# TR4.net
KiCad netlist of a schematic drawn in EAGLE
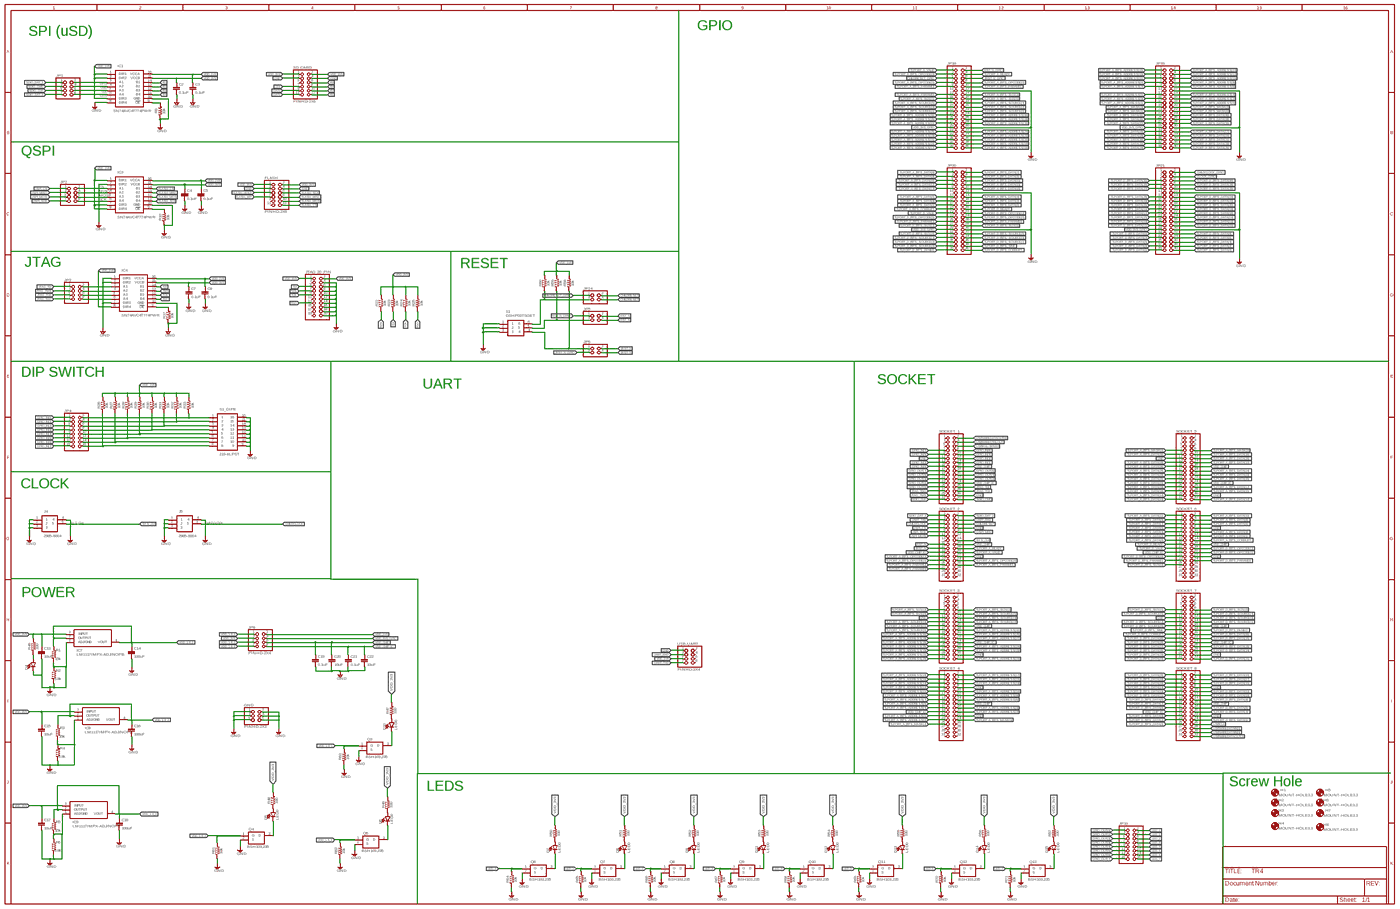
[diagram p0: schematic, sheet 1, overview]
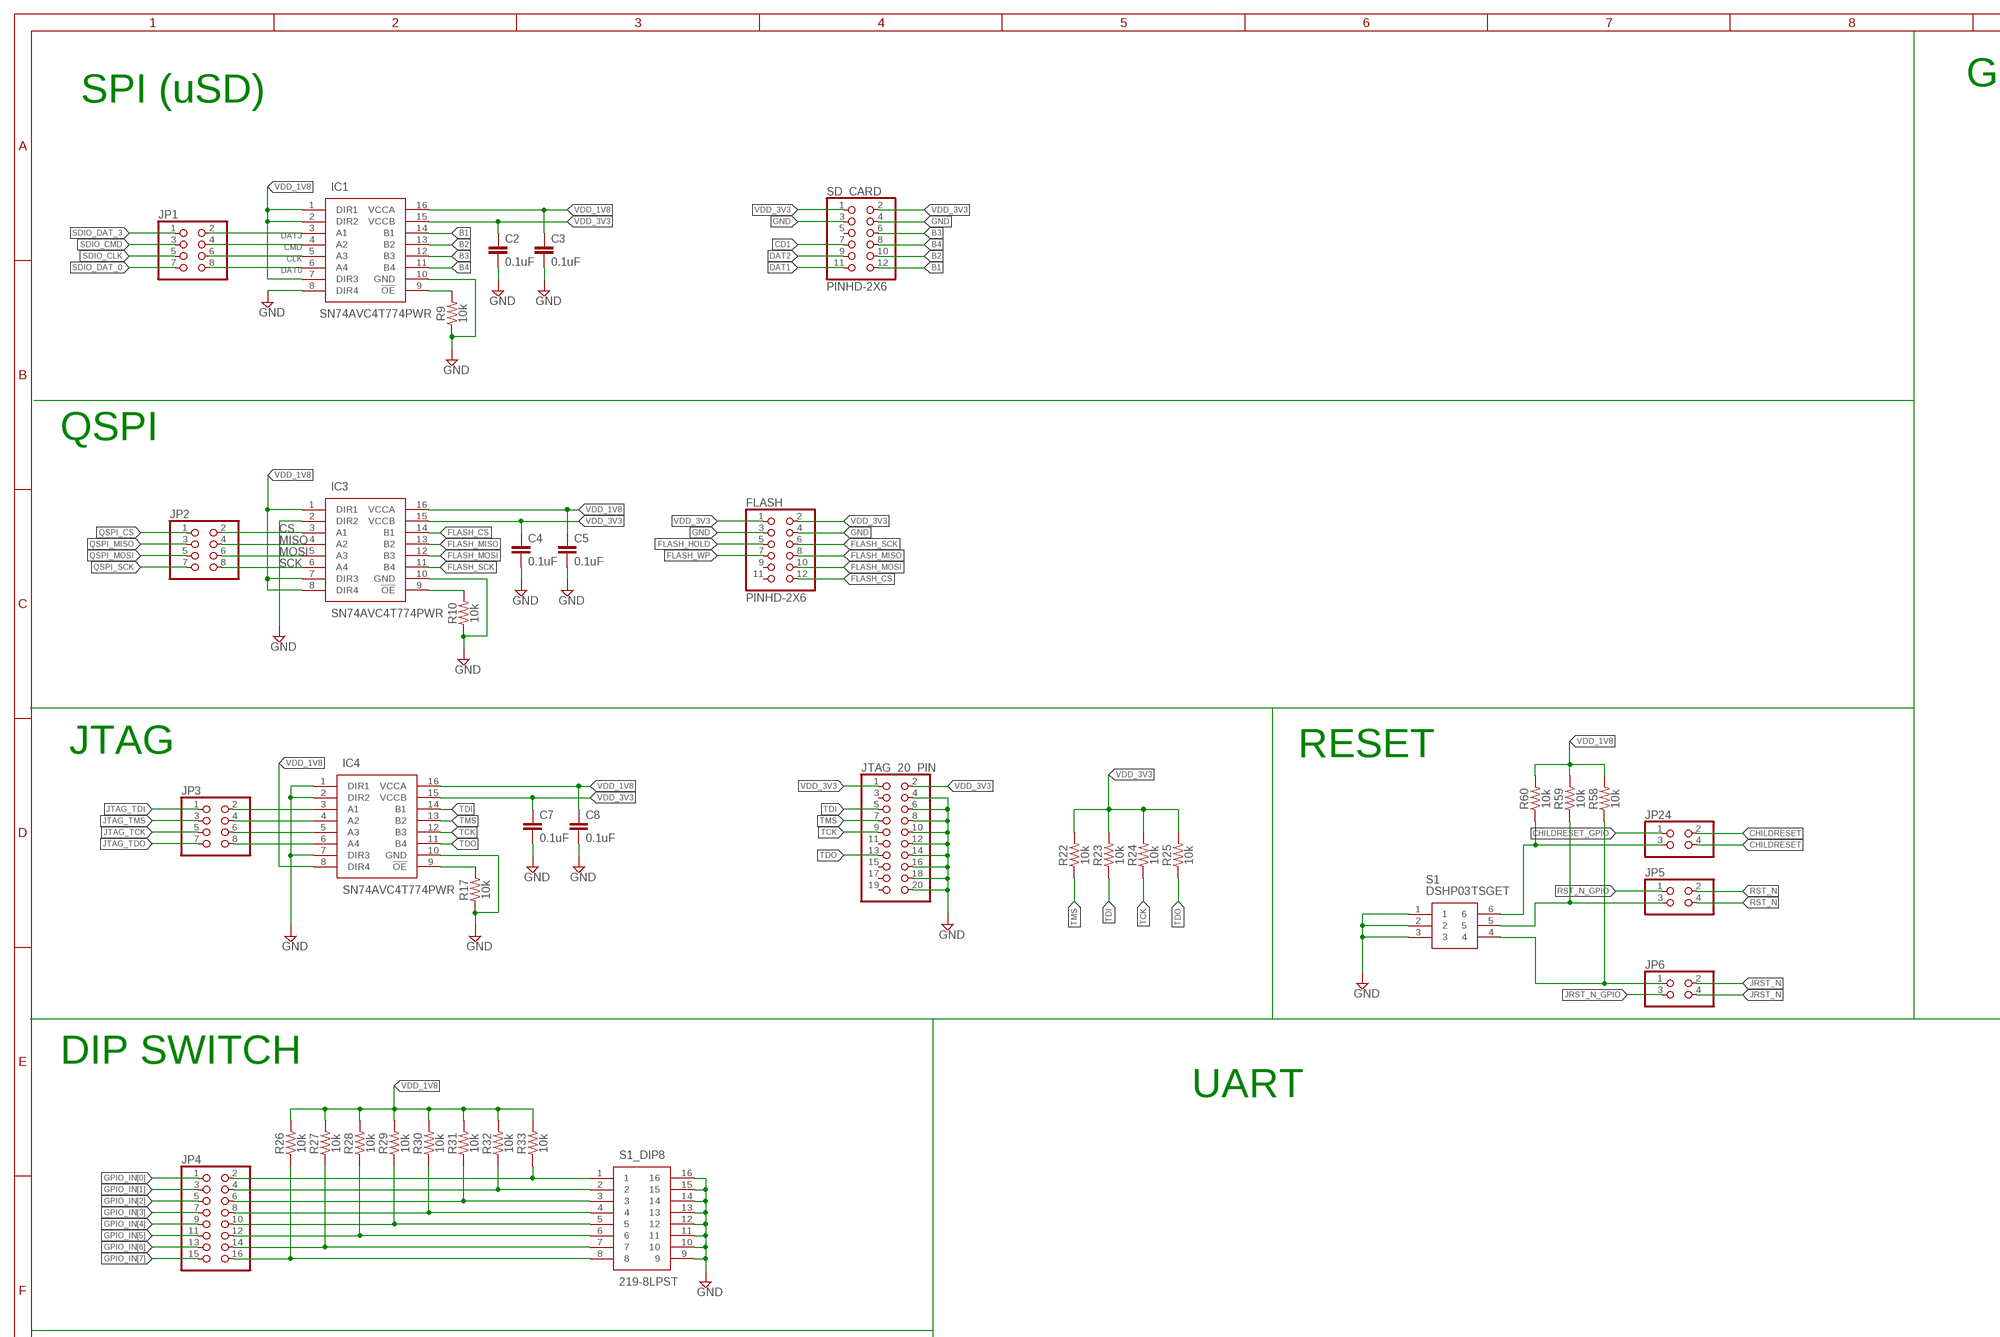
[diagram p1: schematic, sheet 1, part 1 of 4]
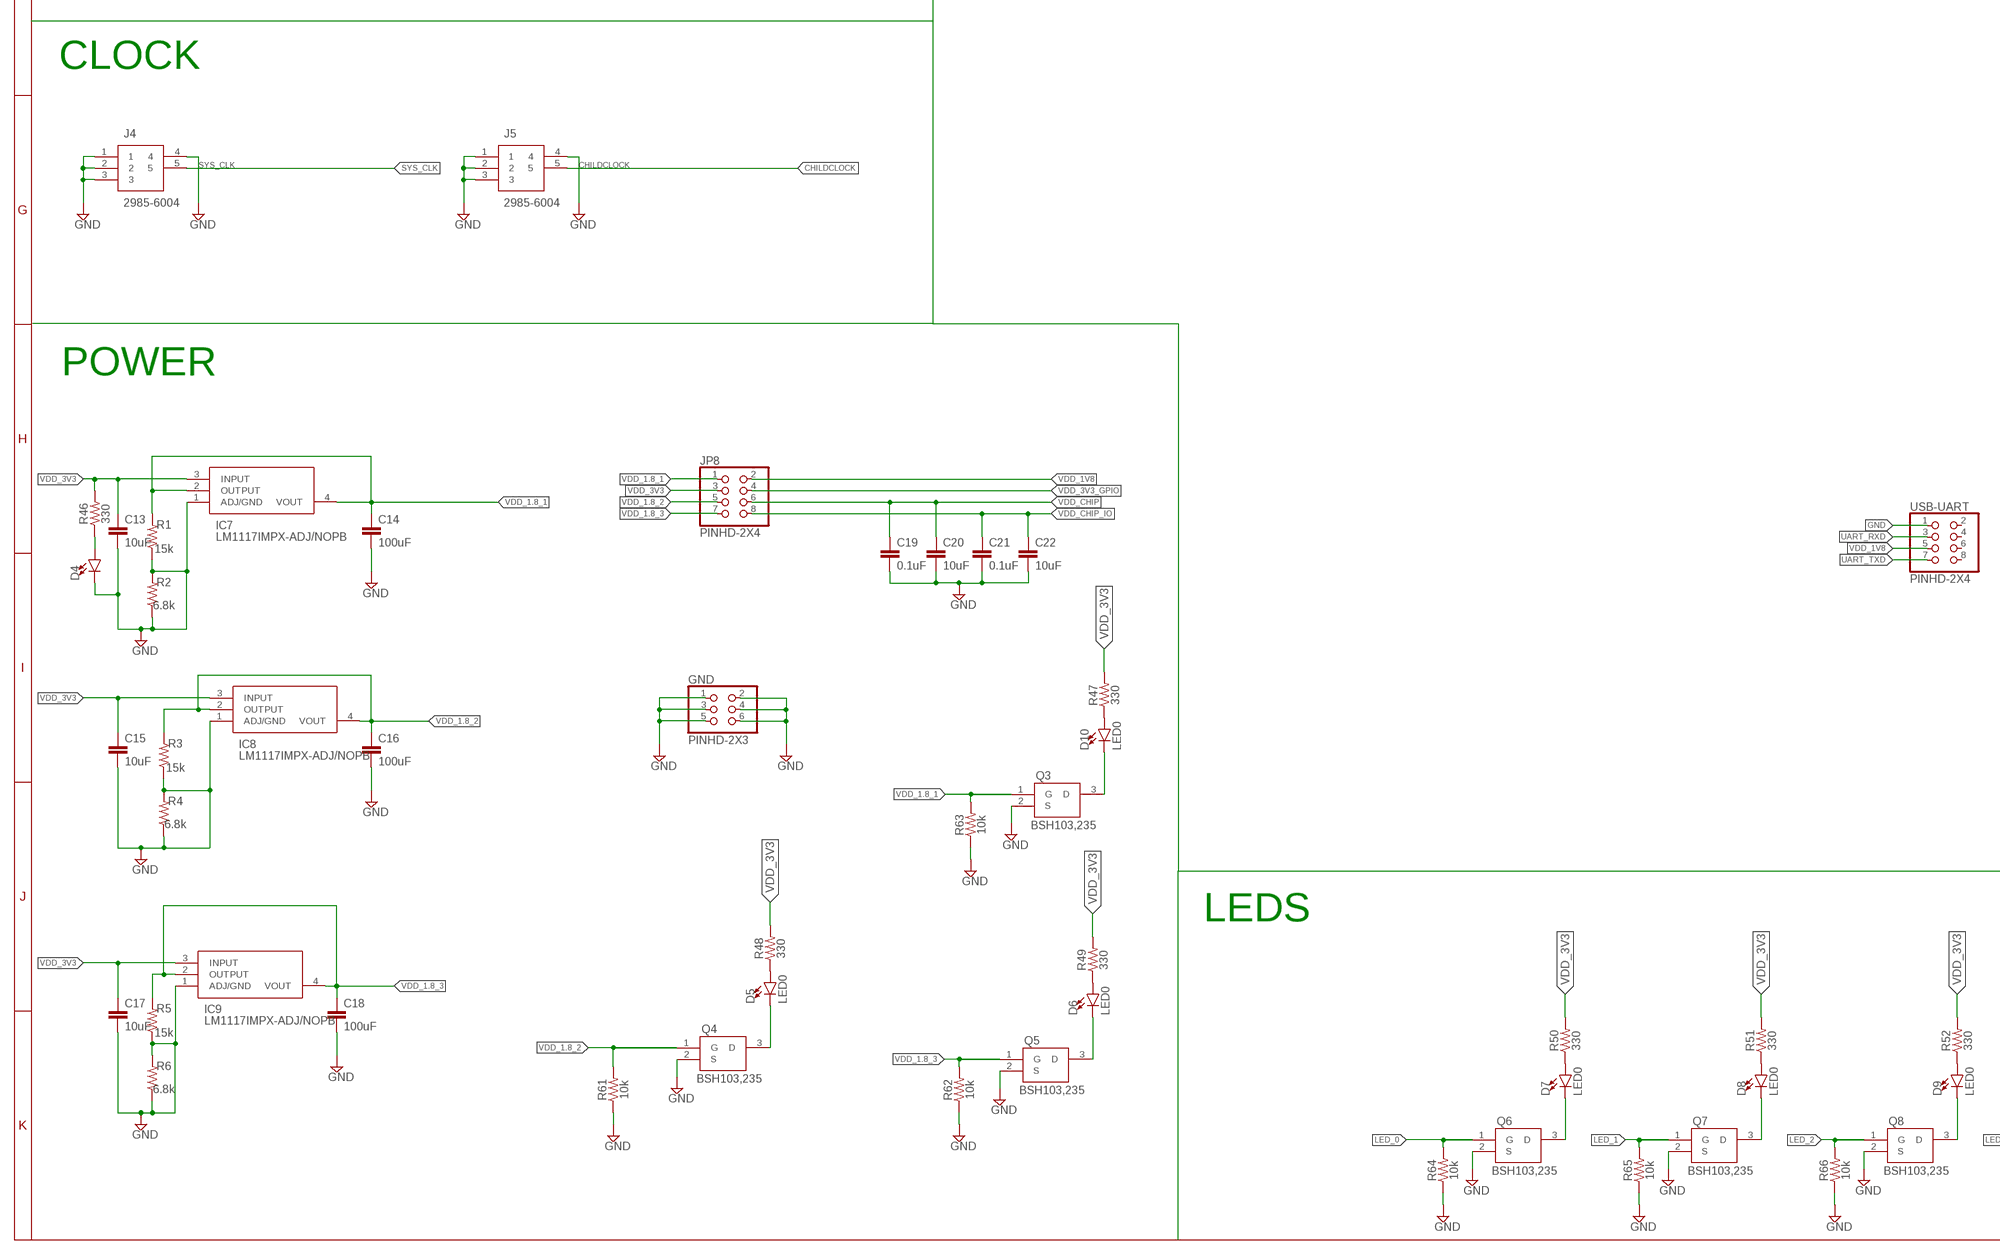
[diagram p2: schematic, sheet 1, part 2 of 4]
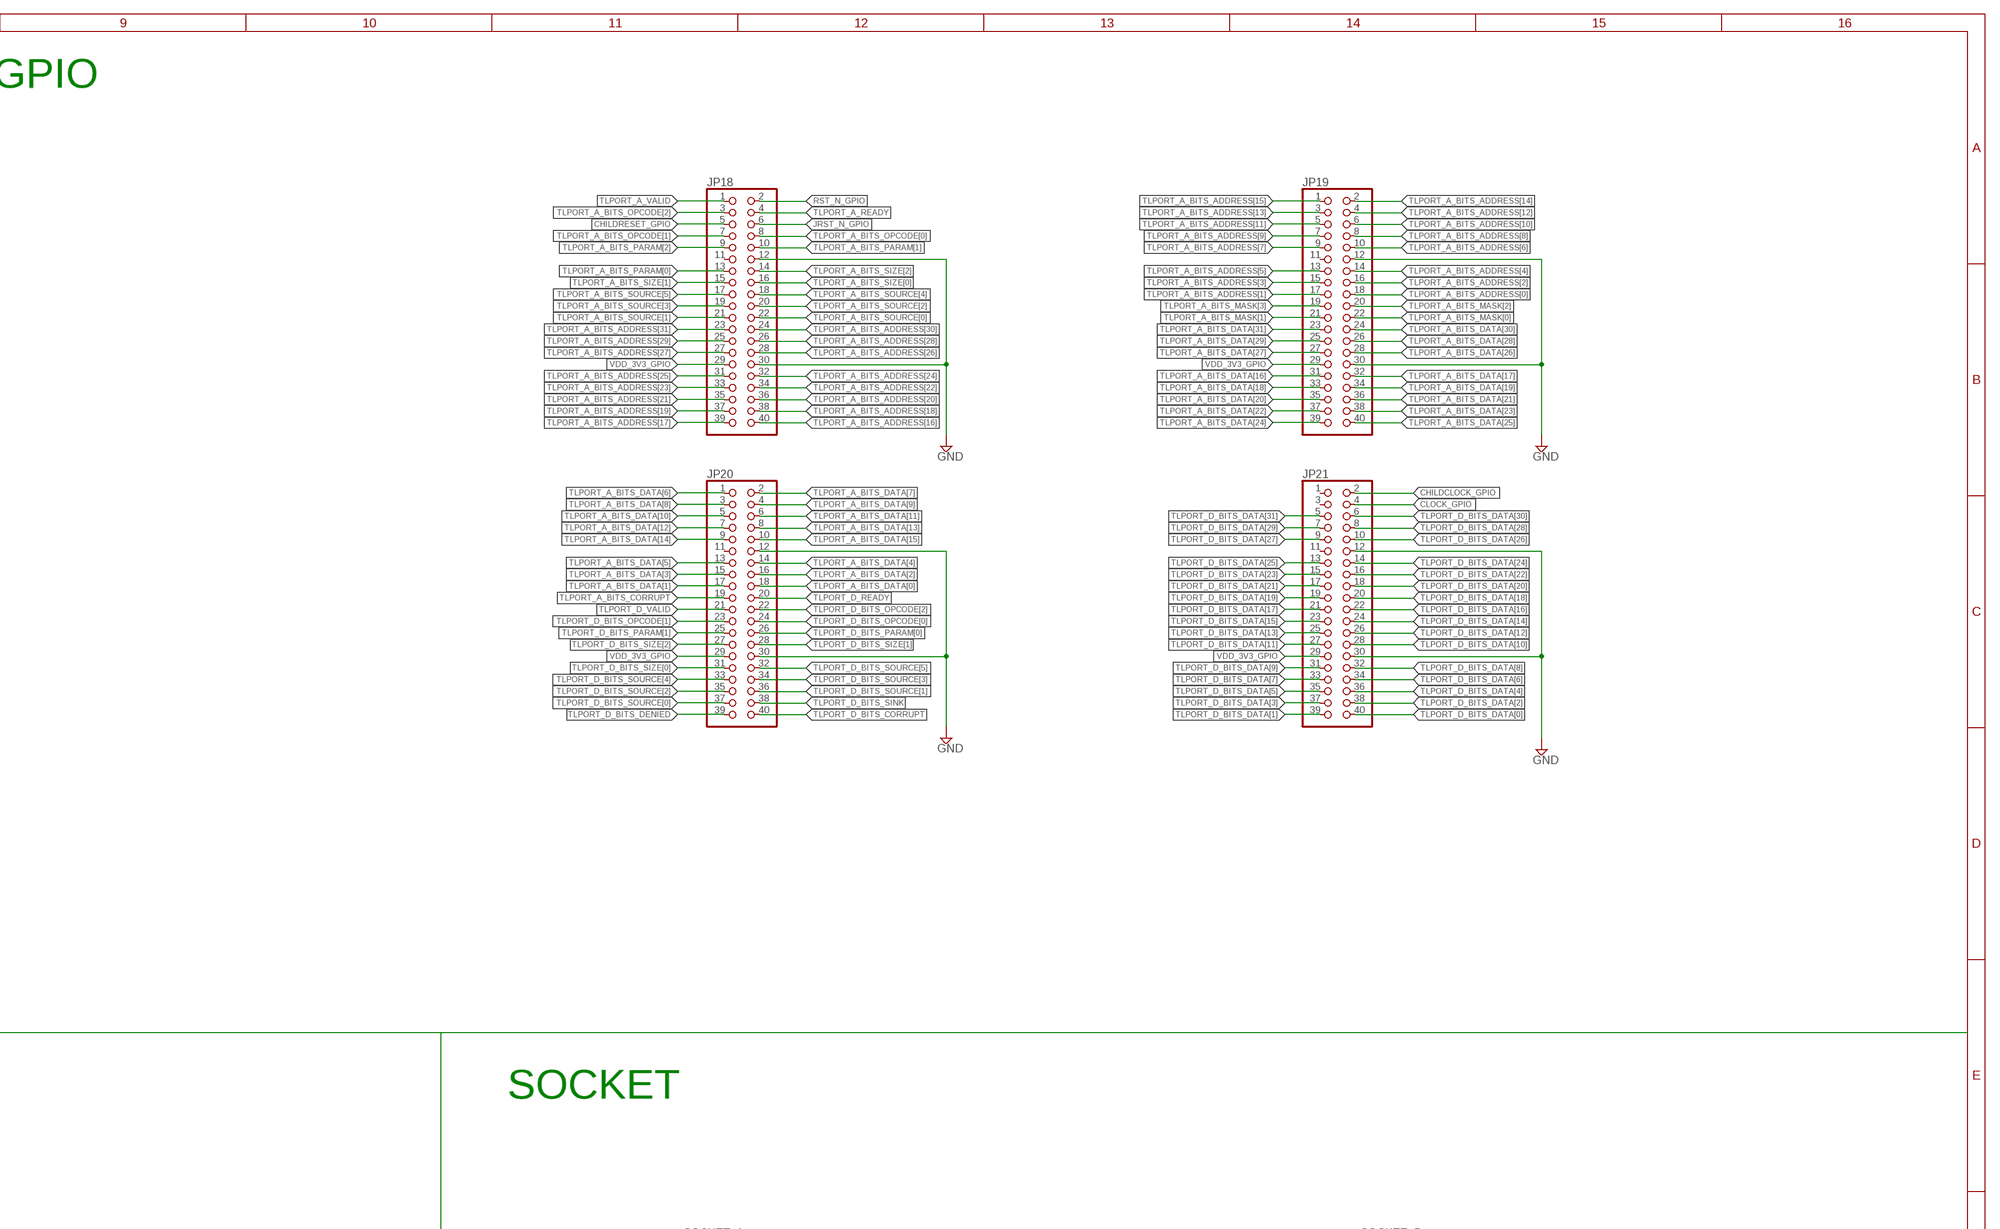
[diagram p3: schematic, sheet 1, part 3 of 4]
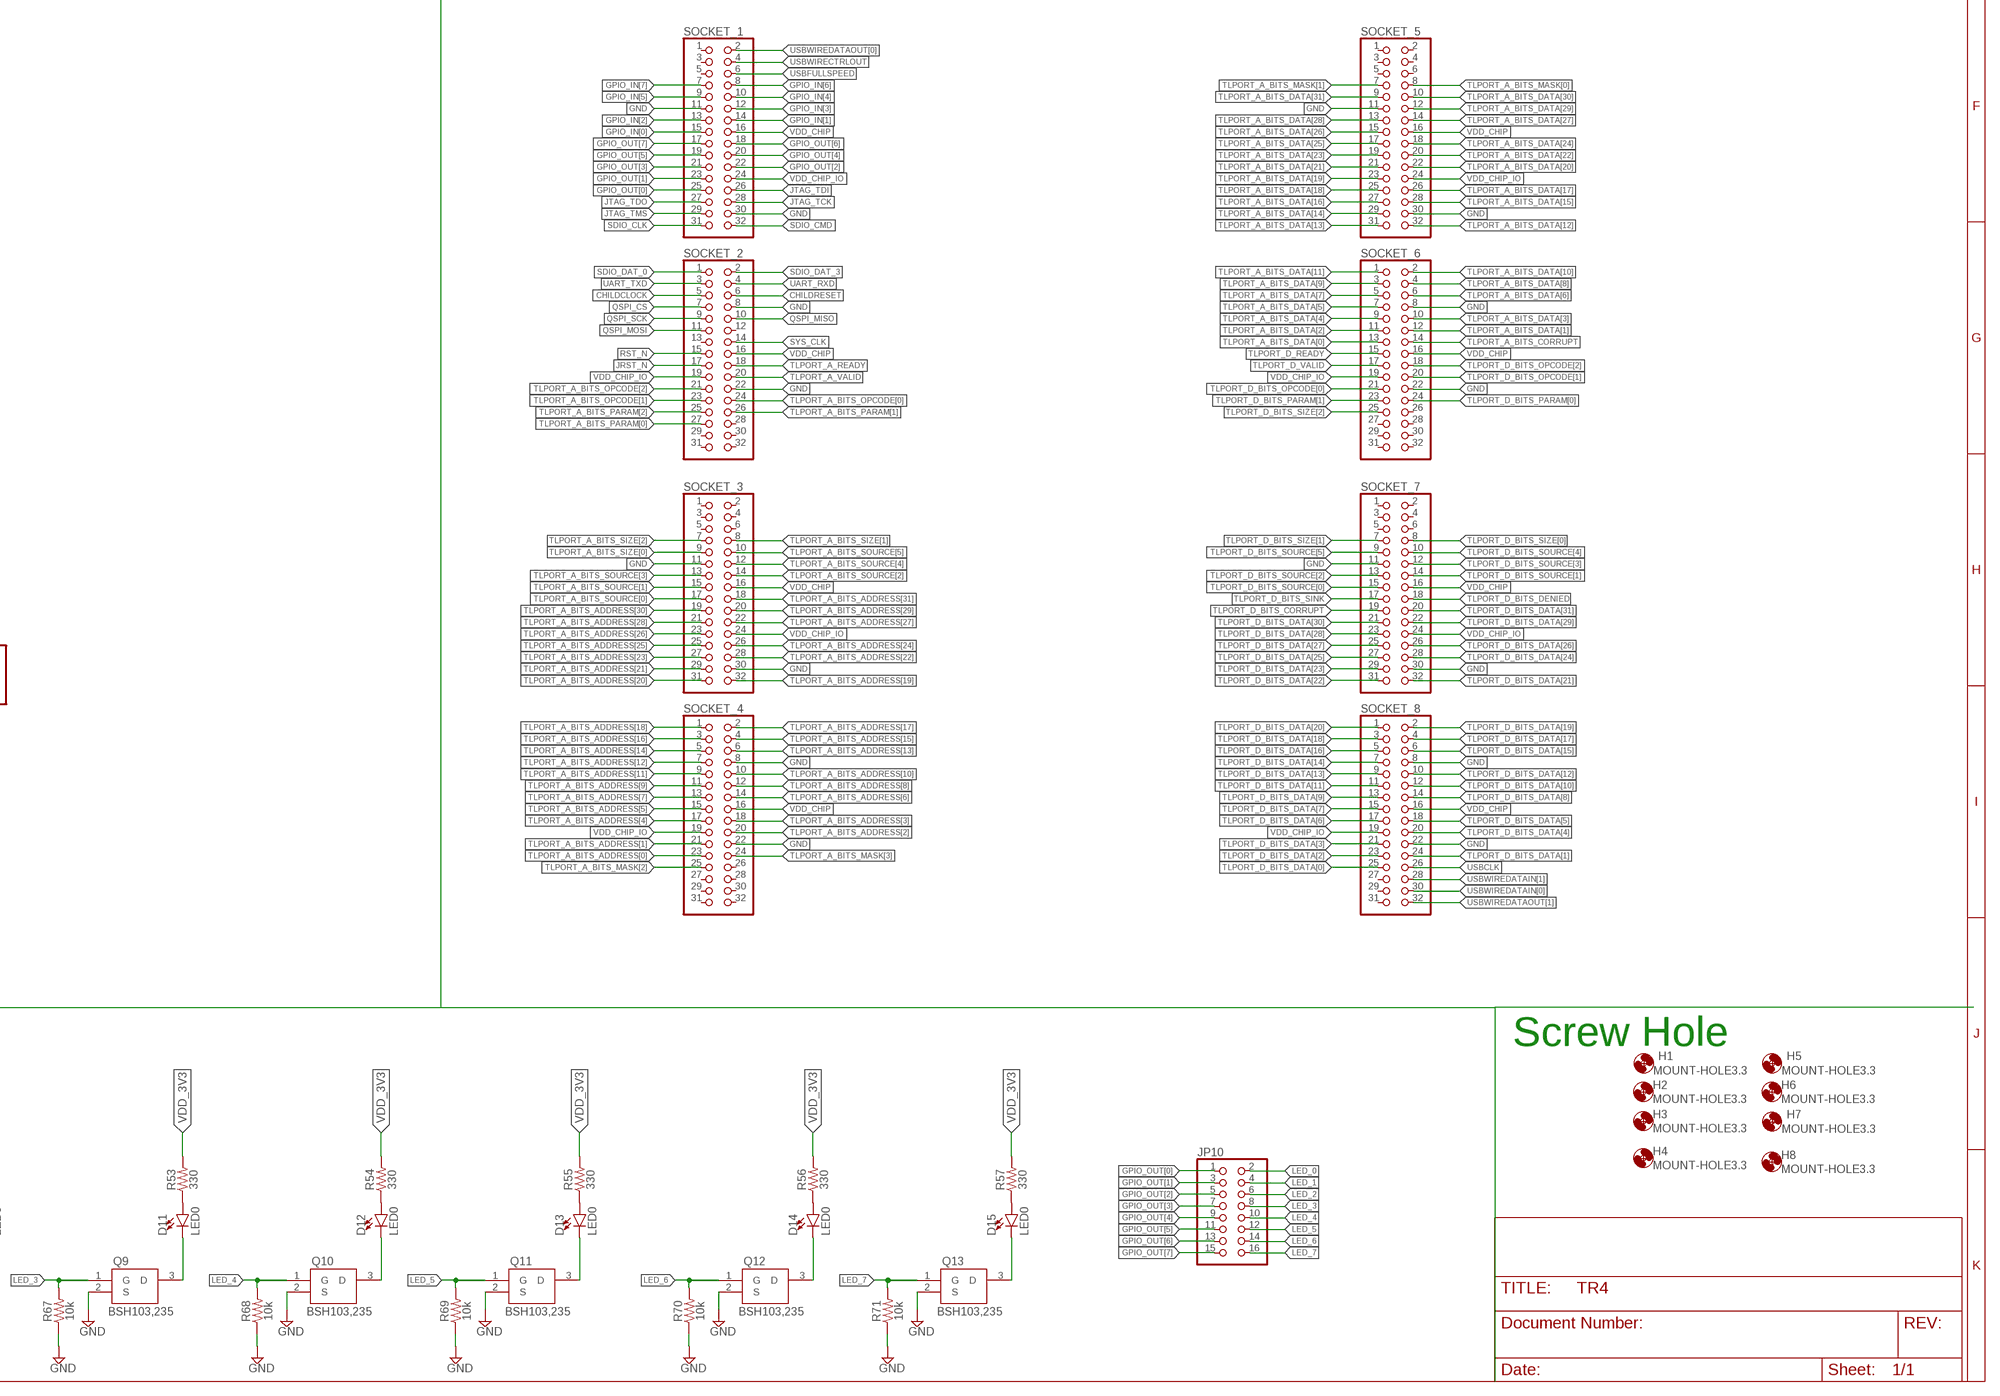
[diagram p4: schematic, sheet 1, part 4 of 4]

(export (version "E")
  (design (tool "Eeschema 10.0.6"))
  (components
    (comp (ref "C2")
      (value "0.1uF")
      (footprint "eagle-import:0603")
      (libsource (lib "eagle-import") (part "0.1UF-0603-25V-5%"))
    )
    (comp (ref "C3")
      (value "0.1uF")
      (footprint "eagle-import:0603")
      (libsource (lib "eagle-import") (part "0.1UF-0603-25V-5%"))
    )
    (comp (ref "C4")
      (value "0.1uF")
      (footprint "eagle-import:0603")
      (libsource (lib "eagle-import") (part "0.1UF-0603-25V-5%"))
    )
    (comp (ref "C5")
      (value "0.1uF")
      (footprint "eagle-import:0603")
      (libsource (lib "eagle-import") (part "0.1UF-0603-25V-5%"))
    )
    (comp (ref "C7")
      (value "0.1uF")
      (footprint "eagle-import:0603")
      (libsource (lib "eagle-import") (part "0.1UF-0603-25V-5%"))
    )
    (comp (ref "C8")
      (value "0.1uF")
      (footprint "eagle-import:0603")
      (libsource (lib "eagle-import") (part "0.1UF-0603-25V-5%"))
    )
    (comp (ref "C13")
      (value "10uF")
      (footprint "eagle-import:0603")
      (libsource (lib "eagle-import") (part "10UF-0603-6.3V-20%"))
    )
    (comp (ref "C14")
      (value "100uF")
      (footprint "eagle-import:0603")
      (libsource (lib "eagle-import") (part "10UF-0603-6.3V-20%"))
    )
    (comp (ref "C15")
      (value "10uF")
      (footprint "eagle-import:0603")
      (libsource (lib "eagle-import") (part "10UF-0603-6.3V-20%"))
    )
    (comp (ref "C16")
      (value "100uF")
      (footprint "eagle-import:0603")
      (libsource (lib "eagle-import") (part "10UF-0603-6.3V-20%"))
    )
    (comp (ref "C17")
      (value "10uF")
      (footprint "eagle-import:0603")
      (libsource (lib "eagle-import") (part "10UF-0603-6.3V-20%"))
    )
    (comp (ref "C18")
      (value "100uF")
      (footprint "eagle-import:0603")
      (libsource (lib "eagle-import") (part "10UF-0603-6.3V-20%"))
    )
    (comp (ref "C19")
      (value "0.1uF")
      (footprint "eagle-import:0603")
      (libsource (lib "eagle-import") (part "0.1UF-0603-25V-5%"))
    )
    (comp (ref "C20")
      (value "10uF")
      (footprint "eagle-import:0603")
      (libsource (lib "eagle-import") (part "10UF-0603-6.3V-20%"))
    )
    (comp (ref "C21")
      (value "0.1uF")
      (footprint "eagle-import:0603")
      (libsource (lib "eagle-import") (part "0.1UF-0603-25V-5%"))
    )
    (comp (ref "C22")
      (value "10uF")
      (footprint "eagle-import:0603")
      (libsource (lib "eagle-import") (part "10UF-0603-6.3V-20%"))
    )
    (comp (ref "D4")
      (value "LED0603")
      (footprint "eagle-import:LED-0603")
      (libsource (lib "eagle-import") (part "LED0603"))
    )
    (comp (ref "D5")
      (value "LED0")
      (footprint "eagle-import:LED-0603")
      (libsource (lib "eagle-import") (part "LED0603"))
    )
    (comp (ref "D6")
      (value "LED0")
      (footprint "eagle-import:LED-0603")
      (libsource (lib "eagle-import") (part "LED0603"))
    )
    (comp (ref "D7")
      (value "LED0")
      (footprint "eagle-import:LED-0603")
      (libsource (lib "eagle-import") (part "LED0603"))
    )
    (comp (ref "D8")
      (value "LED0")
      (footprint "eagle-import:LED-0603")
      (libsource (lib "eagle-import") (part "LED0603"))
    )
    (comp (ref "D9")
      (value "LED0")
      (footprint "eagle-import:LED-0603")
      (libsource (lib "eagle-import") (part "LED0603"))
    )
    (comp (ref "D10")
      (value "LED0")
      (footprint "eagle-import:LED-0603")
      (libsource (lib "eagle-import") (part "LED0603"))
    )
    (comp (ref "D11")
      (value "LED0")
      (footprint "eagle-import:LED-0603")
      (libsource (lib "eagle-import") (part "LED0603"))
    )
    (comp (ref "D12")
      (value "LED0")
      (footprint "eagle-import:LED-0603")
      (libsource (lib "eagle-import") (part "LED0603"))
    )
    (comp (ref "D13")
      (value "LED0")
      (footprint "eagle-import:LED-0603")
      (libsource (lib "eagle-import") (part "LED0603"))
    )
    (comp (ref "D14")
      (value "LED0")
      (footprint "eagle-import:LED-0603")
      (libsource (lib "eagle-import") (part "LED0603"))
    )
    (comp (ref "D15")
      (value "LED0")
      (footprint "eagle-import:LED-0603")
      (libsource (lib "eagle-import") (part "LED0603"))
    )
    (comp (ref "FLASH")
      (value "PINHD-2X6")
      (footprint "eagle-import:2X06")
      (libsource (lib "eagle-import") (part "PINHD-2X6"))
    )
    (comp (ref "GND")
      (value "PINHD-2X3")
      (footprint "eagle-import:2X03")
      (libsource (lib "eagle-import") (part "PINHD-2X3"))
    )
    (comp (ref "H1")
      (value "MOUNT-HOLE3.3")
      (footprint "eagle-import:3,3")
      (libsource (lib "eagle-import") (part "MOUNT-HOLE3.3"))
    )
    (comp (ref "H2")
      (value "MOUNT-HOLE3.3")
      (footprint "eagle-import:3,3")
      (libsource (lib "eagle-import") (part "MOUNT-HOLE3.3"))
    )
    (comp (ref "H3")
      (value "MOUNT-HOLE3.3")
      (footprint "eagle-import:3,3")
      (libsource (lib "eagle-import") (part "MOUNT-HOLE3.3"))
    )
    (comp (ref "H4")
      (value "MOUNT-HOLE3.3")
      (footprint "eagle-import:3,3")
      (libsource (lib "eagle-import") (part "MOUNT-HOLE3.3"))
    )
    (comp (ref "H5")
      (value "MOUNT-HOLE3.3")
      (footprint "eagle-import:3,3")
      (libsource (lib "eagle-import") (part "MOUNT-HOLE3.3"))
    )
    (comp (ref "H6")
      (value "MOUNT-HOLE3.3")
      (footprint "eagle-import:3,3")
      (libsource (lib "eagle-import") (part "MOUNT-HOLE3.3"))
    )
    (comp (ref "H7")
      (value "MOUNT-HOLE3.3")
      (footprint "eagle-import:3,3")
      (libsource (lib "eagle-import") (part "MOUNT-HOLE3.3"))
    )
    (comp (ref "H8")
      (value "MOUNT-HOLE3.3")
      (footprint "eagle-import:3,3")
      (libsource (lib "eagle-import") (part "MOUNT-HOLE3.3"))
    )
    (comp (ref "IC1")
      (value "SN74AVC4T774PWR")
      (footprint "eagle-import:SOP65P640X120-16N")
      (fields (field (name "MOUSER_PART_NUMBER") "595-SN74AVC4T774PWR"))
      (libsource (lib "eagle-import") (part "SN74AVC4T774PWR"))
    )
    (comp (ref "IC3")
      (value "SN74AVC4T774PWR")
      (footprint "eagle-import:SOP65P640X120-16N")
      (fields (field (name "MOUSER_PART_NUMBER") "595-SN74AVC4T774PWR"))
      (libsource (lib "eagle-import") (part "SN74AVC4T774PWR"))
    )
    (comp (ref "IC4")
      (value "SN74AVC4T774PWR")
      (footprint "eagle-import:SOP65P640X120-16N")
      (fields (field (name "MOUSER_PART_NUMBER") "595-SN74AVC4T774PWR"))
      (libsource (lib "eagle-import") (part "SN74AVC4T774PWR"))
    )
    (comp (ref "IC7")
      (value "LM1117IMPX-ADJ/NOPB")
      (footprint "eagle-import:SOT230P700X180-4N")
      (fields
        (field (name "ARROW_PART_NUMBER") "LM1117MP-1.8/NOPB")
        (field (name "MOUSER_PART_NUMBER") "926-LM1117MP-1.8NOPB")
      )
      (libsource (lib "eagle-import") (part "LM1117MP-1.8_NOPB"))
    )
    (comp (ref "IC8")
      (value "LM1117IMPX-ADJ/NOPB")
      (footprint "eagle-import:SOT230P700X180-4N")
      (fields
        (field (name "ARROW_PART_NUMBER") "LM1117MP-1.8/NOPB")
        (field (name "MOUSER_PART_NUMBER") "926-LM1117MP-1.8NOPB")
      )
      (libsource (lib "eagle-import") (part "LM1117MP-1.8_NOPB"))
    )
    (comp (ref "IC9")
      (value "LM1117IMPX-ADJ/NOPB")
      (footprint "eagle-import:SOT230P700X180-4N")
      (fields
        (field (name "ARROW_PART_NUMBER") "LM1117MP-1.8/NOPB")
        (field (name "MOUSER_PART_NUMBER") "926-LM1117MP-1.8NOPB")
      )
      (libsource (lib "eagle-import") (part "LM1117MP-1.8_NOPB"))
    )
    (comp (ref "J4")
      (value "2985-6004")
      (footprint "eagle-import:29856004")
      (fields (field (name "MOUSER_PART_NUMBER") "523-2985-6004"))
      (libsource (lib "eagle-import") (part "2985-6004"))
    )
    (comp (ref "J5")
      (value "2985-6004")
      (footprint "eagle-import:29856004")
      (fields (field (name "MOUSER_PART_NUMBER") "523-2985-6004"))
      (libsource (lib "eagle-import") (part "2985-6004"))
    )
    (comp (ref "JP1")
      (value "PINHD-2X4")
      (footprint "eagle-import:2X04")
      (libsource (lib "eagle-import") (part "adafruit_420_PINHD-2X4"))
    )
    (comp (ref "JP2")
      (value "PINHD-2X4")
      (footprint "eagle-import:2X04")
      (libsource (lib "eagle-import") (part "adafruit_420_PINHD-2X4"))
    )
    (comp (ref "JP3")
      (value "PINHD-2X4")
      (footprint "eagle-import:2X04")
      (libsource (lib "eagle-import") (part "adafruit_420_PINHD-2X4"))
    )
    (comp (ref "JP4")
      (value "PINHD-2X8")
      (footprint "eagle-import:2X08")
      (libsource (lib "eagle-import") (part "PINHD-2X8"))
    )
    (comp (ref "JP5")
      (value "PINHD-2X2")
      (footprint "eagle-import:2X02")
      (libsource (lib "eagle-import") (part "PINHD-2X2"))
    )
    (comp (ref "JP6")
      (value "PINHD-2X2")
      (footprint "eagle-import:2X02")
      (libsource (lib "eagle-import") (part "PINHD-2X2"))
    )
    (comp (ref "JP8")
      (value "PINHD-2X4")
      (footprint "eagle-import:2X04")
      (libsource (lib "eagle-import") (part "PINHD-2X4"))
    )
    (comp (ref "JP10")
      (value "PINHD-2X8")
      (footprint "eagle-import:2X08")
      (libsource (lib "eagle-import") (part "PINHD-2X8"))
    )
    (comp (ref "JP18")
      (value "PINHD-2X20")
      (footprint "eagle-import:2X20")
      (libsource (lib "eagle-import") (part "PINHD-2X20"))
    )
    (comp (ref "JP19")
      (value "PINHD-2X20")
      (footprint "eagle-import:2X20")
      (libsource (lib "eagle-import") (part "PINHD-2X20"))
    )
    (comp (ref "JP20")
      (value "PINHD-2X20")
      (footprint "eagle-import:2X20")
      (libsource (lib "eagle-import") (part "PINHD-2X20"))
    )
    (comp (ref "JP21")
      (value "PINHD-2X20")
      (footprint "eagle-import:2X20")
      (libsource (lib "eagle-import") (part "PINHD-2X20"))
    )
    (comp (ref "JP24")
      (value "PINHD-2X2")
      (footprint "eagle-import:2X02")
      (libsource (lib "eagle-import") (part "PINHD-2X2"))
    )
    (comp (ref "JTAG_20_PIN")
      (value "PINHD-2X10")
      (footprint "eagle-import:2X10")
      (libsource (lib "eagle-import") (part "PINHD-2X10"))
    )
    (comp (ref "Q3")
      (value "BSH103,235")
      (footprint "eagle-import:SOT95P230X110-3N")
      (fields (field (name "MOUSER_PART_NUMBER") "771-BSH103235"))
      (libsource (lib "eagle-import") (part "BSH103,235"))
    )
    (comp (ref "Q4")
      (value "BSH103,235")
      (footprint "eagle-import:SOT95P230X110-3N")
      (fields (field (name "MOUSER_PART_NUMBER") "771-BSH103235"))
      (libsource (lib "eagle-import") (part "BSH103,235"))
    )
    (comp (ref "Q5")
      (value "BSH103,235")
      (footprint "eagle-import:SOT95P230X110-3N")
      (fields (field (name "MOUSER_PART_NUMBER") "771-BSH103235"))
      (libsource (lib "eagle-import") (part "BSH103,235"))
    )
    (comp (ref "Q6")
      (value "BSH103,235")
      (footprint "eagle-import:SOT95P230X110-3N")
      (fields (field (name "MOUSER_PART_NUMBER") "771-BSH103235"))
      (libsource (lib "eagle-import") (part "BSH103,235"))
    )
    (comp (ref "Q7")
      (value "BSH103,235")
      (footprint "eagle-import:SOT95P230X110-3N")
      (fields (field (name "MOUSER_PART_NUMBER") "771-BSH103235"))
      (libsource (lib "eagle-import") (part "BSH103,235"))
    )
    (comp (ref "Q8")
      (value "BSH103,235")
      (footprint "eagle-import:SOT95P230X110-3N")
      (fields (field (name "MOUSER_PART_NUMBER") "771-BSH103235"))
      (libsource (lib "eagle-import") (part "BSH103,235"))
    )
    (comp (ref "Q9")
      (value "BSH103,235")
      (footprint "eagle-import:SOT95P230X110-3N")
      (fields (field (name "MOUSER_PART_NUMBER") "771-BSH103235"))
      (libsource (lib "eagle-import") (part "BSH103,235"))
    )
    (comp (ref "Q10")
      (value "BSH103,235")
      (footprint "eagle-import:SOT95P230X110-3N")
      (fields (field (name "MOUSER_PART_NUMBER") "771-BSH103235"))
      (libsource (lib "eagle-import") (part "BSH103,235"))
    )
    (comp (ref "Q11")
      (value "BSH103,235")
      (footprint "eagle-import:SOT95P230X110-3N")
      (fields (field (name "MOUSER_PART_NUMBER") "771-BSH103235"))
      (libsource (lib "eagle-import") (part "BSH103,235"))
    )
    (comp (ref "Q12")
      (value "BSH103,235")
      (footprint "eagle-import:SOT95P230X110-3N")
      (fields (field (name "MOUSER_PART_NUMBER") "771-BSH103235"))
      (libsource (lib "eagle-import") (part "BSH103,235"))
    )
    (comp (ref "Q13")
      (value "BSH103,235")
      (footprint "eagle-import:SOT95P230X110-3N")
      (fields (field (name "MOUSER_PART_NUMBER") "771-BSH103235"))
      (libsource (lib "eagle-import") (part "BSH103,235"))
    )
    (comp (ref "R1")
      (value "15k")
      (footprint "eagle-import:0603")
      (libsource (lib "eagle-import") (part "15KOHM-0603-1/10W-1%"))
    )
    (comp (ref "R2")
      (value "6.8k")
      (footprint "eagle-import:0603")
      (libsource (lib "eagle-import") (part "6.8KOHM-0603-1/10W-1%"))
    )
    (comp (ref "R3")
      (value "15k")
      (footprint "eagle-import:0603")
      (libsource (lib "eagle-import") (part "15KOHM-0603-1/10W-1%"))
    )
    (comp (ref "R4")
      (value "6.8k")
      (footprint "eagle-import:0603")
      (libsource (lib "eagle-import") (part "6.8KOHM-0603-1/10W-1%"))
    )
    (comp (ref "R5")
      (value "15k")
      (footprint "eagle-import:0603")
      (libsource (lib "eagle-import") (part "15KOHM-0603-1/10W-1%"))
    )
    (comp (ref "R6")
      (value "6.8k")
      (footprint "eagle-import:0603")
      (libsource (lib "eagle-import") (part "6.8KOHM-0603-1/10W-1%"))
    )
    (comp (ref "R9")
      (value "10k")
      (footprint "eagle-import:0603")
      (libsource (lib "eagle-import") (part "10KOHM-0603-1/10W-1%"))
    )
    (comp (ref "R10")
      (value "10k")
      (footprint "eagle-import:0603")
      (libsource (lib "eagle-import") (part "10KOHM-0603-1/10W-1%"))
    )
    (comp (ref "R17")
      (value "10k")
      (footprint "eagle-import:0603")
      (libsource (lib "eagle-import") (part "10KOHM-0603-1/10W-1%"))
    )
    (comp (ref "R22")
      (value "10k")
      (footprint "eagle-import:0603")
      (libsource (lib "eagle-import") (part "10KOHM-0603-1/10W-1%"))
    )
    (comp (ref "R23")
      (value "10k")
      (footprint "eagle-import:0603")
      (libsource (lib "eagle-import") (part "10KOHM-0603-1/10W-1%"))
    )
    (comp (ref "R24")
      (value "10k")
      (footprint "eagle-import:0603")
      (libsource (lib "eagle-import") (part "10KOHM-0603-1/10W-1%"))
    )
    (comp (ref "R25")
      (value "10k")
      (footprint "eagle-import:0603")
      (libsource (lib "eagle-import") (part "10KOHM-0603-1/10W-1%"))
    )
    (comp (ref "R26")
      (value "10k")
      (footprint "eagle-import:0603")
      (libsource (lib "eagle-import") (part "10KOHM-0603-1/10W-1%"))
    )
    (comp (ref "R27")
      (value "10k")
      (footprint "eagle-import:0603")
      (libsource (lib "eagle-import") (part "10KOHM-0603-1/10W-1%"))
    )
    (comp (ref "R28")
      (value "10k")
      (footprint "eagle-import:0603")
      (libsource (lib "eagle-import") (part "10KOHM-0603-1/10W-1%"))
    )
    (comp (ref "R29")
      (value "10k")
      (footprint "eagle-import:0603")
      (libsource (lib "eagle-import") (part "10KOHM-0603-1/10W-1%"))
    )
    (comp (ref "R30")
      (value "10k")
      (footprint "eagle-import:0603")
      (libsource (lib "eagle-import") (part "10KOHM-0603-1/10W-1%"))
    )
    (comp (ref "R31")
      (value "10k")
      (footprint "eagle-import:0603")
      (libsource (lib "eagle-import") (part "10KOHM-0603-1/10W-1%"))
    )
    (comp (ref "R32")
      (value "10k")
      (footprint "eagle-import:0603")
      (libsource (lib "eagle-import") (part "10KOHM-0603-1/10W-1%"))
    )
    (comp (ref "R33")
      (value "10k")
      (footprint "eagle-import:0603")
      (libsource (lib "eagle-import") (part "10KOHM-0603-1/10W-1%"))
    )
    (comp (ref "R46")
      (value "330")
      (footprint "eagle-import:0603")
      (libsource (lib "eagle-import") (part "330OHM-0603-1/10W-1%"))
    )
    (comp (ref "R47")
      (value "330")
      (footprint "eagle-import:0603")
      (libsource (lib "eagle-import") (part "330OHM-0603-1/10W-1%"))
    )
    (comp (ref "R48")
      (value "330")
      (footprint "eagle-import:0603")
      (libsource (lib "eagle-import") (part "330OHM-0603-1/10W-1%"))
    )
    (comp (ref "R49")
      (value "330")
      (footprint "eagle-import:0603")
      (libsource (lib "eagle-import") (part "330OHM-0603-1/10W-1%"))
    )
    (comp (ref "R50")
      (value "330")
      (footprint "eagle-import:0603")
      (libsource (lib "eagle-import") (part "330OHM-0603-1/10W-1%"))
    )
    (comp (ref "R51")
      (value "330")
      (footprint "eagle-import:0603")
      (libsource (lib "eagle-import") (part "330OHM-0603-1/10W-1%"))
    )
    (comp (ref "R52")
      (value "330")
      (footprint "eagle-import:0603")
      (libsource (lib "eagle-import") (part "330OHM-0603-1/10W-1%"))
    )
    (comp (ref "R53")
      (value "330")
      (footprint "eagle-import:0603")
      (libsource (lib "eagle-import") (part "330OHM-0603-1/10W-1%"))
    )
    (comp (ref "R54")
      (value "330")
      (footprint "eagle-import:0603")
      (libsource (lib "eagle-import") (part "330OHM-0603-1/10W-1%"))
    )
    (comp (ref "R55")
      (value "330")
      (footprint "eagle-import:0603")
      (libsource (lib "eagle-import") (part "330OHM-0603-1/10W-1%"))
    )
    (comp (ref "R56")
      (value "330")
      (footprint "eagle-import:0603")
      (libsource (lib "eagle-import") (part "330OHM-0603-1/10W-1%"))
    )
    (comp (ref "R57")
      (value "330")
      (footprint "eagle-import:0603")
      (libsource (lib "eagle-import") (part "330OHM-0603-1/10W-1%"))
    )
    (comp (ref "R58")
      (value "10k")
      (footprint "eagle-import:0603")
      (libsource (lib "eagle-import") (part "10KOHM-0603-1/10W-1%"))
    )
    (comp (ref "R59")
      (value "10k")
      (footprint "eagle-import:0603")
      (libsource (lib "eagle-import") (part "10KOHM-0603-1/10W-1%"))
    )
    (comp (ref "R60")
      (value "10k")
      (footprint "eagle-import:0603")
      (libsource (lib "eagle-import") (part "10KOHM-0603-1/10W-1%"))
    )
    (comp (ref "R61")
      (value "10k")
      (footprint "eagle-import:0603")
      (libsource (lib "eagle-import") (part "10KOHM-0603-1/10W-1%"))
    )
    (comp (ref "R62")
      (value "10k")
      (footprint "eagle-import:0603")
      (libsource (lib "eagle-import") (part "10KOHM-0603-1/10W-1%"))
    )
    (comp (ref "R63")
      (value "10k")
      (footprint "eagle-import:0603")
      (libsource (lib "eagle-import") (part "10KOHM-0603-1/10W-1%"))
    )
    (comp (ref "R64")
      (value "10k")
      (footprint "eagle-import:0603")
      (libsource (lib "eagle-import") (part "10KOHM-0603-1/10W-1%"))
    )
    (comp (ref "R65")
      (value "10k")
      (footprint "eagle-import:0603")
      (libsource (lib "eagle-import") (part "10KOHM-0603-1/10W-1%"))
    )
    (comp (ref "R66")
      (value "10k")
      (footprint "eagle-import:0603")
      (libsource (lib "eagle-import") (part "10KOHM-0603-1/10W-1%"))
    )
    (comp (ref "R67")
      (value "10k")
      (footprint "eagle-import:0603")
      (libsource (lib "eagle-import") (part "10KOHM-0603-1/10W-1%"))
    )
    (comp (ref "R68")
      (value "10k")
      (footprint "eagle-import:0603")
      (libsource (lib "eagle-import") (part "10KOHM-0603-1/10W-1%"))
    )
    (comp (ref "R69")
      (value "10k")
      (footprint "eagle-import:0603")
      (libsource (lib "eagle-import") (part "10KOHM-0603-1/10W-1%"))
    )
    (comp (ref "R70")
      (value "10k")
      (footprint "eagle-import:0603")
      (libsource (lib "eagle-import") (part "10KOHM-0603-1/10W-1%"))
    )
    (comp (ref "R71")
      (value "10k")
      (footprint "eagle-import:0603")
      (libsource (lib "eagle-import") (part "10KOHM-0603-1/10W-1%"))
    )
    (comp (ref "S1")
      (value "DSHP03TSGET")
      (footprint "eagle-import:SOT127P835X260-6N")
      (libsource (lib "eagle-import") (part "DSHP03TSGET"))
    )
    (comp (ref "S1_DIP8")
      (value "219-8LPST")
      (footprint "eagle-import:2198LPST")
      (fields (field (name "MOUSER_PART_NUMBER") "774-2198LPST"))
      (libsource (lib "eagle-import") (part "219-8LPST"))
    )
    (comp (ref "SD_CARD")
      (value "PINHD-2X6")
      (footprint "eagle-import:2X06")
      (libsource (lib "eagle-import") (part "PINHD-2X6"))
    )
    (comp (ref "SOCKET_1")
      (value "PINHD-2X16")
      (footprint "eagle-import:2X16")
      (libsource (lib "eagle-import") (part "PINHD-2X16"))
    )
    (comp (ref "SOCKET_2")
      (value "PINHD-2X16")
      (footprint "eagle-import:2X16")
      (libsource (lib "eagle-import") (part "PINHD-2X16"))
    )
    (comp (ref "SOCKET_3")
      (value "PINHD-2X16")
      (footprint "eagle-import:2X16")
      (libsource (lib "eagle-import") (part "PINHD-2X16"))
    )
    (comp (ref "SOCKET_4")
      (value "PINHD-2X16")
      (footprint "eagle-import:2X16")
      (libsource (lib "eagle-import") (part "PINHD-2X16"))
    )
    (comp (ref "SOCKET_5")
      (value "PINHD-2X16")
      (footprint "eagle-import:2X16")
      (libsource (lib "eagle-import") (part "PINHD-2X16"))
    )
    (comp (ref "SOCKET_6")
      (value "PINHD-2X16")
      (footprint "eagle-import:2X16")
      (libsource (lib "eagle-import") (part "PINHD-2X16"))
    )
    (comp (ref "SOCKET_7")
      (value "PINHD-2X16")
      (footprint "eagle-import:2X16")
      (libsource (lib "eagle-import") (part "PINHD-2X16"))
    )
    (comp (ref "SOCKET_8")
      (value "PINHD-2X16")
      (footprint "eagle-import:2X16")
      (libsource (lib "eagle-import") (part "PINHD-2X16"))
    )
    (comp (ref "USB-UART")
      (value "PINHD-2X4")
      (footprint "eagle-import:2X04")
      (libsource (lib "eagle-import") (part "PINHD-2X4"))
    )
  )
  (nets
    (net (code "1") (name "/CLK") (class "Default")
      (node (ref "IC1") (pin "5") (pinfunction "A3_5") (pintype "bidirectional"))
      (node (ref "JP1") (pin "6") (pinfunction "6_6") (pintype "passive"))
    )
    (net (code "2") (name "/CMD") (class "Default")
      (node (ref "IC1") (pin "4") (pinfunction "A2_4") (pintype "bidirectional"))
      (node (ref "JP1") (pin "4") (pinfunction "4_4") (pintype "passive"))
    )
    (net (code "3") (name "/CS") (class "Default")
      (node (ref "IC3") (pin "3") (pinfunction "A1_3") (pintype "bidirectional"))
      (node (ref "JP2") (pin "2") (pinfunction "2_2") (pintype "passive"))
    )
    (net (code "4") (name "/DAT0") (class "Default")
      (node (ref "IC1") (pin "6") (pinfunction "A4_6") (pintype "bidirectional"))
      (node (ref "JP1") (pin "8") (pinfunction "8_8") (pintype "passive"))
    )
    (net (code "5") (name "/DAT3") (class "Default")
      (node (ref "IC1") (pin "3") (pinfunction "A1_3") (pintype "bidirectional"))
      (node (ref "JP1") (pin "2") (pinfunction "2_2") (pintype "passive"))
    )
    (net (code "6") (name "/MISO") (class "Default")
      (node (ref "IC3") (pin "4") (pinfunction "A2_4") (pintype "bidirectional"))
      (node (ref "JP2") (pin "4") (pinfunction "4_4") (pintype "passive"))
    )
    (net (code "7") (name "/MOSI") (class "Default")
      (node (ref "IC3") (pin "5") (pinfunction "A3_5") (pintype "bidirectional"))
      (node (ref "JP2") (pin "6") (pinfunction "6_6") (pintype "passive"))
    )
    (net (code "8") (name "/SCK") (class "Default")
      (node (ref "IC3") (pin "6") (pinfunction "A4_6") (pintype "bidirectional"))
      (node (ref "JP2") (pin "8") (pinfunction "8_8") (pintype "passive"))
    )
    (net (code "9") (name "B1") (class "Default")
      (node (ref "IC1") (pin "14") (pinfunction "B1_14") (pintype "bidirectional"))
      (node (ref "SD_CARD") (pin "12") (pinfunction "12_12") (pintype "passive"))
    )
    (net (code "10") (name "B2") (class "Default")
      (node (ref "IC1") (pin "13") (pinfunction "B2_13") (pintype "bidirectional"))
      (node (ref "SD_CARD") (pin "10") (pinfunction "10_10") (pintype "passive"))
    )
    (net (code "11") (name "B3") (class "Default")
      (node (ref "IC1") (pin "12") (pinfunction "B3_12") (pintype "bidirectional"))
      (node (ref "SD_CARD") (pin "6") (pinfunction "6_6") (pintype "passive"))
    )
    (net (code "12") (name "B4") (class "Default")
      (node (ref "IC1") (pin "11") (pinfunction "B4_11") (pintype "bidirectional"))
      (node (ref "SD_CARD") (pin "8") (pinfunction "8_8") (pintype "passive"))
    )
    (net (code "13") (name "CD1") (class "Default")
      (node (ref "SD_CARD") (pin "7") (pinfunction "7_7") (pintype "passive"))
    )
    (net (code "14") (name "CHILDCLOCK") (class "Default")
      (node (ref "J5") (pin "5") (pinfunction "5_5") (pintype "bidirectional"))
      (node (ref "SOCKET_2") (pin "5") (pinfunction "5_5") (pintype "passive"))
    )
    (net (code "15") (name "CHILDCLOCK_GPIO") (class "Default")
      (node (ref "JP21") (pin "2") (pinfunction "2_2") (pintype "passive"))
    )
    (net (code "16") (name "CHILDRESET") (class "Default")
      (node (ref "JP24") (pin "2") (pinfunction "2_2") (pintype "passive"))
      (node (ref "JP24") (pin "4") (pinfunction "4_4") (pintype "passive"))
      (node (ref "SOCKET_2") (pin "6") (pinfunction "6_6") (pintype "passive"))
    )
    (net (code "17") (name "CHILDRESET_GPIO") (class "Default")
      (node (ref "JP18") (pin "5") (pinfunction "5_5") (pintype "passive"))
      (node (ref "JP24") (pin "1") (pinfunction "1_1") (pintype "passive"))
    )
    (net (code "18") (name "CLOCK_GPIO") (class "Default")
      (node (ref "JP21") (pin "4") (pinfunction "4_4") (pintype "passive"))
    )
    (net (code "19") (name "DAT1") (class "Default")
      (node (ref "SD_CARD") (pin "11") (pinfunction "11_11") (pintype "passive"))
    )
    (net (code "20") (name "DAT2") (class "Default")
      (node (ref "SD_CARD") (pin "9") (pinfunction "9_9") (pintype "passive"))
    )
    (net (code "21") (name "FLASH_CS") (class "Default")
      (node (ref "FLASH") (pin "12") (pinfunction "12_12") (pintype "passive"))
      (node (ref "IC3") (pin "14") (pinfunction "B1_14") (pintype "bidirectional"))
    )
    (net (code "22") (name "FLASH_HOLD") (class "Default")
      (node (ref "FLASH") (pin "5") (pinfunction "5_5") (pintype "passive"))
    )
    (net (code "23") (name "FLASH_MISO") (class "Default")
      (node (ref "FLASH") (pin "8") (pinfunction "8_8") (pintype "passive"))
      (node (ref "IC3") (pin "13") (pinfunction "B2_13") (pintype "bidirectional"))
    )
    (net (code "24") (name "FLASH_MOSI") (class "Default")
      (node (ref "FLASH") (pin "10") (pinfunction "10_10") (pintype "passive"))
      (node (ref "IC3") (pin "12") (pinfunction "B3_12") (pintype "bidirectional"))
    )
    (net (code "25") (name "FLASH_SCK") (class "Default")
      (node (ref "FLASH") (pin "6") (pinfunction "6_6") (pintype "passive"))
      (node (ref "IC3") (pin "11") (pinfunction "B4_11") (pintype "bidirectional"))
    )
    (net (code "26") (name "FLASH_WP") (class "Default")
      (node (ref "FLASH") (pin "7") (pinfunction "7_7") (pintype "passive"))
    )
    (net (code "27") (name "GND") (class "Default")
      (node (ref "C13") (pin "2") (pinfunction "2_2") (pintype "passive"))
      (node (ref "C14") (pin "2") (pinfunction "2_2") (pintype "passive"))
      (node (ref "C15") (pin "2") (pinfunction "2_2") (pintype "passive"))
      (node (ref "C16") (pin "2") (pinfunction "2_2") (pintype "passive"))
      (node (ref "C17") (pin "2") (pinfunction "2_2") (pintype "passive"))
      (node (ref "C18") (pin "2") (pinfunction "2_2") (pintype "passive"))
      (node (ref "C19") (pin "2") (pinfunction "2_2") (pintype "passive"))
      (node (ref "C2") (pin "2") (pinfunction "2_2") (pintype "passive"))
      (node (ref "C20") (pin "2") (pinfunction "2_2") (pintype "passive"))
      (node (ref "C21") (pin "2") (pinfunction "2_2") (pintype "passive"))
      (node (ref "C22") (pin "2") (pinfunction "2_2") (pintype "passive"))
      (node (ref "C3") (pin "2") (pinfunction "2_2") (pintype "passive"))
      (node (ref "C4") (pin "2") (pinfunction "2_2") (pintype "passive"))
      (node (ref "C5") (pin "2") (pinfunction "2_2") (pintype "passive"))
      (node (ref "C7") (pin "2") (pinfunction "2_2") (pintype "passive"))
      (node (ref "C8") (pin "2") (pinfunction "2_2") (pintype "passive"))
      (node (ref "D4") (pin "C") (pinfunction "C_C") (pintype "passive"))
      (node (ref "FLASH") (pin "3") (pinfunction "3_3") (pintype "passive"))
      (node (ref "FLASH") (pin "4") (pinfunction "4_4") (pintype "passive"))
      (node (ref "GND") (pin "1") (pinfunction "1_1") (pintype "passive"))
      (node (ref "GND") (pin "2") (pinfunction "2_2") (pintype "passive"))
      (node (ref "GND") (pin "3") (pinfunction "3_3") (pintype "passive"))
      (node (ref "GND") (pin "4") (pinfunction "4_4") (pintype "passive"))
      (node (ref "GND") (pin "5") (pinfunction "5_5") (pintype "passive"))
      (node (ref "GND") (pin "6") (pinfunction "6_6") (pintype "passive"))
      (node (ref "IC1") (pin "10") (pinfunction "GND_10") (pintype "bidirectional"))
      (node (ref "IC1") (pin "8") (pinfunction "DIR4_8") (pintype "bidirectional"))
      (node (ref "IC3") (pin "10") (pinfunction "GND_10") (pintype "bidirectional"))
      (node (ref "IC3") (pin "2") (pinfunction "DIR2_2") (pintype "bidirectional"))
      (node (ref "IC4") (pin "1") (pinfunction "DIR1_1") (pintype "bidirectional"))
      (node (ref "IC4") (pin "10") (pinfunction "GND_10") (pintype "bidirectional"))
      (node (ref "IC4") (pin "2") (pinfunction "DIR2_2") (pintype "bidirectional"))
      (node (ref "IC4") (pin "7") (pinfunction "DIR3_7") (pintype "bidirectional"))
      (node (ref "IC7") (pin "1") (pinfunction "ADJ/GND_1") (pintype "bidirectional"))
      (node (ref "IC8") (pin "1") (pinfunction "ADJ/GND_1") (pintype "bidirectional"))
      (node (ref "IC9") (pin "1") (pinfunction "ADJ/GND_1") (pintype "bidirectional"))
      (node (ref "J4") (pin "1") (pinfunction "1_1") (pintype "bidirectional"))
      (node (ref "J4") (pin "2") (pinfunction "2_2") (pintype "bidirectional"))
      (node (ref "J4") (pin "3") (pinfunction "3_3") (pintype "bidirectional"))
      (node (ref "J4") (pin "4") (pinfunction "4_4") (pintype "bidirectional"))
      (node (ref "J5") (pin "1") (pinfunction "1_1") (pintype "bidirectional"))
      (node (ref "J5") (pin "2") (pinfunction "2_2") (pintype "bidirectional"))
      (node (ref "J5") (pin "3") (pinfunction "3_3") (pintype "bidirectional"))
      (node (ref "J5") (pin "4") (pinfunction "4_4") (pintype "bidirectional"))
      (node (ref "JP18") (pin "12") (pinfunction "12_12") (pintype "passive"))
      (node (ref "JP18") (pin "30") (pinfunction "30_30") (pintype "passive"))
      (node (ref "JP19") (pin "12") (pinfunction "12_12") (pintype "passive"))
      (node (ref "JP19") (pin "30") (pinfunction "30_30") (pintype "passive"))
      (node (ref "JP20") (pin "12") (pinfunction "12_12") (pintype "passive"))
      (node (ref "JP20") (pin "30") (pinfunction "30_30") (pintype "passive"))
      (node (ref "JP21") (pin "12") (pinfunction "12_12") (pintype "passive"))
      (node (ref "JP21") (pin "30") (pinfunction "30_30") (pintype "passive"))
      (node (ref "JTAG_20_PIN") (pin "10") (pinfunction "10_10") (pintype "passive"))
      (node (ref "JTAG_20_PIN") (pin "12") (pinfunction "12_12") (pintype "passive"))
      (node (ref "JTAG_20_PIN") (pin "14") (pinfunction "14_14") (pintype "passive"))
      (node (ref "JTAG_20_PIN") (pin "16") (pinfunction "16_16") (pintype "passive"))
      (node (ref "JTAG_20_PIN") (pin "18") (pinfunction "18_18") (pintype "passive"))
      (node (ref "JTAG_20_PIN") (pin "20") (pinfunction "20_20") (pintype "passive"))
      (node (ref "JTAG_20_PIN") (pin "4") (pinfunction "4_4") (pintype "passive"))
      (node (ref "JTAG_20_PIN") (pin "6") (pinfunction "6_6") (pintype "passive"))
      (node (ref "JTAG_20_PIN") (pin "8") (pinfunction "8_8") (pintype "passive"))
      (node (ref "Q10") (pin "2") (pinfunction "S_2") (pintype "bidirectional"))
      (node (ref "Q11") (pin "2") (pinfunction "S_2") (pintype "bidirectional"))
      (node (ref "Q12") (pin "2") (pinfunction "S_2") (pintype "bidirectional"))
      (node (ref "Q13") (pin "2") (pinfunction "S_2") (pintype "bidirectional"))
      (node (ref "Q3") (pin "2") (pinfunction "S_2") (pintype "bidirectional"))
      (node (ref "Q4") (pin "2") (pinfunction "S_2") (pintype "bidirectional"))
      (node (ref "Q5") (pin "2") (pinfunction "S_2") (pintype "bidirectional"))
      (node (ref "Q6") (pin "2") (pinfunction "S_2") (pintype "bidirectional"))
      (node (ref "Q7") (pin "2") (pinfunction "S_2") (pintype "bidirectional"))
      (node (ref "Q8") (pin "2") (pinfunction "S_2") (pintype "bidirectional"))
      (node (ref "Q9") (pin "2") (pinfunction "S_2") (pintype "bidirectional"))
      (node (ref "R1") (pin "1") (pinfunction "1_1") (pintype "passive"))
      (node (ref "R10") (pin "1") (pinfunction "1_1") (pintype "passive"))
      (node (ref "R17") (pin "1") (pinfunction "1_1") (pintype "passive"))
      (node (ref "R2") (pin "1") (pinfunction "1_1") (pintype "passive"))
      (node (ref "R2") (pin "2") (pinfunction "2_2") (pintype "passive"))
      (node (ref "R3") (pin "1") (pinfunction "1_1") (pintype "passive"))
      (node (ref "R4") (pin "1") (pinfunction "1_1") (pintype "passive"))
      (node (ref "R4") (pin "2") (pinfunction "2_2") (pintype "passive"))
      (node (ref "R5") (pin "1") (pinfunction "1_1") (pintype "passive"))
      (node (ref "R6") (pin "1") (pinfunction "1_1") (pintype "passive"))
      (node (ref "R6") (pin "2") (pinfunction "2_2") (pintype "passive"))
      (node (ref "R61") (pin "1") (pinfunction "1_1") (pintype "passive"))
      (node (ref "R62") (pin "1") (pinfunction "1_1") (pintype "passive"))
      (node (ref "R63") (pin "1") (pinfunction "1_1") (pintype "passive"))
      (node (ref "R64") (pin "1") (pinfunction "1_1") (pintype "passive"))
      (node (ref "R65") (pin "1") (pinfunction "1_1") (pintype "passive"))
      (node (ref "R66") (pin "1") (pinfunction "1_1") (pintype "passive"))
      (node (ref "R67") (pin "1") (pinfunction "1_1") (pintype "passive"))
      (node (ref "R68") (pin "1") (pinfunction "1_1") (pintype "passive"))
      (node (ref "R69") (pin "1") (pinfunction "1_1") (pintype "passive"))
      (node (ref "R70") (pin "1") (pinfunction "1_1") (pintype "passive"))
      (node (ref "R71") (pin "1") (pinfunction "1_1") (pintype "passive"))
      (node (ref "R9") (pin "1") (pinfunction "1_1") (pintype "passive"))
      (node (ref "S1") (pin "1") (pinfunction "1_1") (pintype "bidirectional"))
      (node (ref "S1") (pin "2") (pinfunction "2_2") (pintype "bidirectional"))
      (node (ref "S1") (pin "3") (pinfunction "3_3") (pintype "bidirectional"))
      (node (ref "S1_DIP8") (pin "10") (pinfunction "10_10") (pintype "bidirectional"))
      (node (ref "S1_DIP8") (pin "11") (pinfunction "11_11") (pintype "bidirectional"))
      (node (ref "S1_DIP8") (pin "12") (pinfunction "12_12") (pintype "bidirectional"))
      (node (ref "S1_DIP8") (pin "13") (pinfunction "13_13") (pintype "bidirectional"))
      (node (ref "S1_DIP8") (pin "14") (pinfunction "14_14") (pintype "bidirectional"))
      (node (ref "S1_DIP8") (pin "15") (pinfunction "15_15") (pintype "bidirectional"))
      (node (ref "S1_DIP8") (pin "16") (pinfunction "16_16") (pintype "bidirectional"))
      (node (ref "S1_DIP8") (pin "9") (pinfunction "9_9") (pintype "bidirectional"))
      (node (ref "SD_CARD") (pin "3") (pinfunction "3_3") (pintype "passive"))
      (node (ref "SD_CARD") (pin "4") (pinfunction "4_4") (pintype "passive"))
      (node (ref "SOCKET_1") (pin "11") (pinfunction "11_11") (pintype "passive"))
      (node (ref "SOCKET_1") (pin "30") (pinfunction "30_30") (pintype "passive"))
      (node (ref "SOCKET_2") (pin "22") (pinfunction "22_22") (pintype "passive"))
      (node (ref "SOCKET_2") (pin "8") (pinfunction "8_8") (pintype "passive"))
      (node (ref "SOCKET_3") (pin "11") (pinfunction "11_11") (pintype "passive"))
      (node (ref "SOCKET_3") (pin "30") (pinfunction "30_30") (pintype "passive"))
      (node (ref "SOCKET_4") (pin "22") (pinfunction "22_22") (pintype "passive"))
      (node (ref "SOCKET_4") (pin "8") (pinfunction "8_8") (pintype "passive"))
      (node (ref "SOCKET_5") (pin "11") (pinfunction "11_11") (pintype "passive"))
      (node (ref "SOCKET_5") (pin "30") (pinfunction "30_30") (pintype "passive"))
      (node (ref "SOCKET_6") (pin "22") (pinfunction "22_22") (pintype "passive"))
      (node (ref "SOCKET_6") (pin "8") (pinfunction "8_8") (pintype "passive"))
      (node (ref "SOCKET_7") (pin "11") (pinfunction "11_11") (pintype "passive"))
      (node (ref "SOCKET_7") (pin "30") (pinfunction "30_30") (pintype "passive"))
      (node (ref "SOCKET_8") (pin "22") (pinfunction "22_22") (pintype "passive"))
      (node (ref "SOCKET_8") (pin "8") (pinfunction "8_8") (pintype "passive"))
      (node (ref "USB-UART") (pin "1") (pinfunction "1_1") (pintype "passive"))
    )
    (net (code "28") (name "GPIO_IN[0]") (class "Default")
      (node (ref "JP4") (pin "1") (pinfunction "1_1") (pintype "passive"))
      (node (ref "SOCKET_1") (pin "15") (pinfunction "15_15") (pintype "passive"))
    )
    (net (code "29") (name "GPIO_IN[1]") (class "Default")
      (node (ref "JP4") (pin "3") (pinfunction "3_3") (pintype "passive"))
      (node (ref "SOCKET_1") (pin "14") (pinfunction "14_14") (pintype "passive"))
    )
    (net (code "30") (name "GPIO_IN[2]") (class "Default")
      (node (ref "JP4") (pin "5") (pinfunction "5_5") (pintype "passive"))
      (node (ref "SOCKET_1") (pin "13") (pinfunction "13_13") (pintype "passive"))
    )
    (net (code "31") (name "GPIO_IN[3]") (class "Default")
      (node (ref "JP4") (pin "7") (pinfunction "7_7") (pintype "passive"))
      (node (ref "SOCKET_1") (pin "12") (pinfunction "12_12") (pintype "passive"))
    )
    (net (code "32") (name "GPIO_IN[4]") (class "Default")
      (node (ref "JP4") (pin "9") (pinfunction "9_9") (pintype "passive"))
      (node (ref "SOCKET_1") (pin "10") (pinfunction "10_10") (pintype "passive"))
    )
    (net (code "33") (name "GPIO_IN[5]") (class "Default")
      (node (ref "JP4") (pin "11") (pinfunction "11_11") (pintype "passive"))
      (node (ref "SOCKET_1") (pin "9") (pinfunction "9_9") (pintype "passive"))
    )
    (net (code "34") (name "GPIO_IN[6]") (class "Default")
      (node (ref "JP4") (pin "13") (pinfunction "13_13") (pintype "passive"))
      (node (ref "SOCKET_1") (pin "8") (pinfunction "8_8") (pintype "passive"))
    )
    (net (code "35") (name "GPIO_IN[7]") (class "Default")
      (node (ref "JP4") (pin "15") (pinfunction "15_15") (pintype "passive"))
      (node (ref "SOCKET_1") (pin "7") (pinfunction "7_7") (pintype "passive"))
    )
    (net (code "36") (name "GPIO_OUT[0]") (class "Default")
      (node (ref "JP10") (pin "1") (pinfunction "1_1") (pintype "passive"))
      (node (ref "SOCKET_1") (pin "25") (pinfunction "25_25") (pintype "passive"))
    )
    (net (code "37") (name "GPIO_OUT[1]") (class "Default")
      (node (ref "JP10") (pin "3") (pinfunction "3_3") (pintype "passive"))
      (node (ref "SOCKET_1") (pin "23") (pinfunction "23_23") (pintype "passive"))
    )
    (net (code "38") (name "GPIO_OUT[2]") (class "Default")
      (node (ref "JP10") (pin "5") (pinfunction "5_5") (pintype "passive"))
      (node (ref "SOCKET_1") (pin "22") (pinfunction "22_22") (pintype "passive"))
    )
    (net (code "39") (name "GPIO_OUT[3]") (class "Default")
      (node (ref "JP10") (pin "7") (pinfunction "7_7") (pintype "passive"))
      (node (ref "SOCKET_1") (pin "21") (pinfunction "21_21") (pintype "passive"))
    )
    (net (code "40") (name "GPIO_OUT[4]") (class "Default")
      (node (ref "JP10") (pin "9") (pinfunction "9_9") (pintype "passive"))
      (node (ref "SOCKET_1") (pin "20") (pinfunction "20_20") (pintype "passive"))
    )
    (net (code "41") (name "GPIO_OUT[5]") (class "Default")
      (node (ref "JP10") (pin "11") (pinfunction "11_11") (pintype "passive"))
      (node (ref "SOCKET_1") (pin "19") (pinfunction "19_19") (pintype "passive"))
    )
    (net (code "42") (name "GPIO_OUT[6]") (class "Default")
      (node (ref "JP10") (pin "13") (pinfunction "13_13") (pintype "passive"))
      (node (ref "SOCKET_1") (pin "18") (pinfunction "18_18") (pintype "passive"))
    )
    (net (code "43") (name "GPIO_OUT[7]") (class "Default")
      (node (ref "JP10") (pin "15") (pinfunction "15_15") (pintype "passive"))
      (node (ref "SOCKET_1") (pin "17") (pinfunction "17_17") (pintype "passive"))
    )
    (net (code "44") (name "JRST_N") (class "Default")
      (node (ref "JP6") (pin "2") (pinfunction "2_2") (pintype "passive"))
      (node (ref "JP6") (pin "4") (pinfunction "4_4") (pintype "passive"))
      (node (ref "SOCKET_2") (pin "17") (pinfunction "17_17") (pintype "passive"))
    )
    (net (code "45") (name "JRST_N_GPIO") (class "Default")
      (node (ref "JP18") (pin "6") (pinfunction "6_6") (pintype "passive"))
      (node (ref "JP6") (pin "3") (pinfunction "3_3") (pintype "passive"))
    )
    (net (code "46") (name "JTAG_TCK") (class "Default")
      (node (ref "JP3") (pin "5") (pinfunction "5_5") (pintype "passive"))
      (node (ref "SOCKET_1") (pin "28") (pinfunction "28_28") (pintype "passive"))
    )
    (net (code "47") (name "JTAG_TDI") (class "Default")
      (node (ref "JP3") (pin "1") (pinfunction "1_1") (pintype "passive"))
      (node (ref "SOCKET_1") (pin "26") (pinfunction "26_26") (pintype "passive"))
    )
    (net (code "48") (name "JTAG_TDO") (class "Default")
      (node (ref "JP3") (pin "7") (pinfunction "7_7") (pintype "passive"))
      (node (ref "SOCKET_1") (pin "27") (pinfunction "27_27") (pintype "passive"))
    )
    (net (code "49") (name "JTAG_TMS") (class "Default")
      (node (ref "JP3") (pin "3") (pinfunction "3_3") (pintype "passive"))
      (node (ref "SOCKET_1") (pin "29") (pinfunction "29_29") (pintype "passive"))
    )
    (net (code "50") (name "LED_0") (class "Default")
      (node (ref "JP10") (pin "2") (pinfunction "2_2") (pintype "passive"))
      (node (ref "Q6") (pin "1") (pinfunction "G_1") (pintype "bidirectional"))
      (node (ref "R64") (pin "2") (pinfunction "2_2") (pintype "passive"))
    )
    (net (code "51") (name "LED_1") (class "Default")
      (node (ref "JP10") (pin "4") (pinfunction "4_4") (pintype "passive"))
      (node (ref "Q7") (pin "1") (pinfunction "G_1") (pintype "bidirectional"))
      (node (ref "R65") (pin "2") (pinfunction "2_2") (pintype "passive"))
    )
    (net (code "52") (name "LED_2") (class "Default")
      (node (ref "JP10") (pin "6") (pinfunction "6_6") (pintype "passive"))
      (node (ref "Q8") (pin "1") (pinfunction "G_1") (pintype "bidirectional"))
      (node (ref "R66") (pin "2") (pinfunction "2_2") (pintype "passive"))
    )
    (net (code "53") (name "LED_3") (class "Default")
      (node (ref "JP10") (pin "8") (pinfunction "8_8") (pintype "passive"))
      (node (ref "Q9") (pin "1") (pinfunction "G_1") (pintype "bidirectional"))
      (node (ref "R67") (pin "2") (pinfunction "2_2") (pintype "passive"))
    )
    (net (code "54") (name "LED_4") (class "Default")
      (node (ref "JP10") (pin "10") (pinfunction "10_10") (pintype "passive"))
      (node (ref "Q10") (pin "1") (pinfunction "G_1") (pintype "bidirectional"))
      (node (ref "R68") (pin "2") (pinfunction "2_2") (pintype "passive"))
    )
    (net (code "55") (name "LED_5") (class "Default")
      (node (ref "JP10") (pin "12") (pinfunction "12_12") (pintype "passive"))
      (node (ref "Q11") (pin "1") (pinfunction "G_1") (pintype "bidirectional"))
      (node (ref "R69") (pin "2") (pinfunction "2_2") (pintype "passive"))
    )
    (net (code "56") (name "LED_6") (class "Default")
      (node (ref "JP10") (pin "14") (pinfunction "14_14") (pintype "passive"))
      (node (ref "Q12") (pin "1") (pinfunction "G_1") (pintype "bidirectional"))
      (node (ref "R70") (pin "2") (pinfunction "2_2") (pintype "passive"))
    )
    (net (code "57") (name "LED_7") (class "Default")
      (node (ref "JP10") (pin "16") (pinfunction "16_16") (pintype "passive"))
      (node (ref "Q13") (pin "1") (pinfunction "G_1") (pintype "bidirectional"))
      (node (ref "R71") (pin "2") (pinfunction "2_2") (pintype "passive"))
    )
    (net (code "58") (name "Net-(D4-PadA)") (class "Default")
      (node (ref "D4") (pin "A") (pinfunction "A_A") (pintype "passive"))
      (node (ref "R46") (pin "1") (pinfunction "1_1") (pintype "passive"))
    )
    (net (code "59") (name "Net-(D5-PadA)") (class "Default")
      (node (ref "D5") (pin "A") (pinfunction "A_A") (pintype "passive"))
      (node (ref "R48") (pin "1") (pinfunction "1_1") (pintype "passive"))
    )
    (net (code "60") (name "Net-(D6-PadA)") (class "Default")
      (node (ref "D6") (pin "A") (pinfunction "A_A") (pintype "passive"))
      (node (ref "R49") (pin "1") (pinfunction "1_1") (pintype "passive"))
    )
    (net (code "61") (name "Net-(D7-PadA)") (class "Default")
      (node (ref "D7") (pin "A") (pinfunction "A_A") (pintype "passive"))
      (node (ref "R50") (pin "1") (pinfunction "1_1") (pintype "passive"))
    )
    (net (code "62") (name "Net-(D8-PadA)") (class "Default")
      (node (ref "D8") (pin "A") (pinfunction "A_A") (pintype "passive"))
      (node (ref "R51") (pin "1") (pinfunction "1_1") (pintype "passive"))
    )
    (net (code "63") (name "Net-(D9-PadA)") (class "Default")
      (node (ref "D9") (pin "A") (pinfunction "A_A") (pintype "passive"))
      (node (ref "R52") (pin "1") (pinfunction "1_1") (pintype "passive"))
    )
    (net (code "64") (name "Net-(D10-PadA)") (class "Default")
      (node (ref "D10") (pin "A") (pinfunction "A_A") (pintype "passive"))
      (node (ref "R47") (pin "1") (pinfunction "1_1") (pintype "passive"))
    )
    (net (code "65") (name "Net-(D11-PadA)") (class "Default")
      (node (ref "D11") (pin "A") (pinfunction "A_A") (pintype "passive"))
      (node (ref "R53") (pin "1") (pinfunction "1_1") (pintype "passive"))
    )
    (net (code "66") (name "Net-(D12-PadA)") (class "Default")
      (node (ref "D12") (pin "A") (pinfunction "A_A") (pintype "passive"))
      (node (ref "R54") (pin "1") (pinfunction "1_1") (pintype "passive"))
    )
    (net (code "67") (name "Net-(D13-PadA)") (class "Default")
      (node (ref "D13") (pin "A") (pinfunction "A_A") (pintype "passive"))
      (node (ref "R55") (pin "1") (pinfunction "1_1") (pintype "passive"))
    )
    (net (code "68") (name "Net-(D14-PadA)") (class "Default")
      (node (ref "D14") (pin "A") (pinfunction "A_A") (pintype "passive"))
      (node (ref "R56") (pin "1") (pinfunction "1_1") (pintype "passive"))
    )
    (net (code "69") (name "Net-(D15-PadA)") (class "Default")
      (node (ref "D15") (pin "A") (pinfunction "A_A") (pintype "passive"))
      (node (ref "R57") (pin "1") (pinfunction "1_1") (pintype "passive"))
    )
    (net (code "70") (name "Net-(IC1-~{OE})") (class "Default")
      (node (ref "IC1") (pin "9") (pinfunction "~{OE}_9") (pintype "bidirectional"))
      (node (ref "R9") (pin "2") (pinfunction "2_2") (pintype "passive"))
    )
    (net (code "71") (name "Net-(IC3-~{OE})") (class "Default")
      (node (ref "IC3") (pin "9") (pinfunction "~{OE}_9") (pintype "bidirectional"))
      (node (ref "R10") (pin "2") (pinfunction "2_2") (pintype "passive"))
    )
    (net (code "72") (name "Net-(IC4-A1)") (class "Default")
      (node (ref "IC4") (pin "3") (pinfunction "A1_3") (pintype "bidirectional"))
      (node (ref "JP3") (pin "2") (pinfunction "2_2") (pintype "passive"))
    )
    (net (code "73") (name "Net-(IC4-A2)") (class "Default")
      (node (ref "IC4") (pin "4") (pinfunction "A2_4") (pintype "bidirectional"))
      (node (ref "JP3") (pin "4") (pinfunction "4_4") (pintype "passive"))
    )
    (net (code "74") (name "Net-(IC4-A3)") (class "Default")
      (node (ref "IC4") (pin "5") (pinfunction "A3_5") (pintype "bidirectional"))
      (node (ref "JP3") (pin "6") (pinfunction "6_6") (pintype "passive"))
    )
    (net (code "75") (name "Net-(IC4-A4)") (class "Default")
      (node (ref "IC4") (pin "6") (pinfunction "A4_6") (pintype "bidirectional"))
      (node (ref "JP3") (pin "8") (pinfunction "8_8") (pintype "passive"))
    )
    (net (code "76") (name "Net-(IC4-~{OE})") (class "Default")
      (node (ref "IC4") (pin "9") (pinfunction "~{OE}_9") (pintype "bidirectional"))
      (node (ref "R17") (pin "2") (pinfunction "2_2") (pintype "passive"))
    )
    (net (code "77") (name "Net-(JP4-Pad2)") (class "Default")
      (node (ref "JP4") (pin "2") (pinfunction "2_2") (pintype "passive"))
      (node (ref "R33") (pin "1") (pinfunction "1_1") (pintype "passive"))
      (node (ref "S1_DIP8") (pin "1") (pinfunction "1_1") (pintype "bidirectional"))
    )
    (net (code "78") (name "Net-(JP4-Pad4)") (class "Default")
      (node (ref "JP4") (pin "4") (pinfunction "4_4") (pintype "passive"))
      (node (ref "R32") (pin "1") (pinfunction "1_1") (pintype "passive"))
      (node (ref "S1_DIP8") (pin "2") (pinfunction "2_2") (pintype "bidirectional"))
    )
    (net (code "79") (name "Net-(JP4-Pad6)") (class "Default")
      (node (ref "JP4") (pin "6") (pinfunction "6_6") (pintype "passive"))
      (node (ref "R31") (pin "1") (pinfunction "1_1") (pintype "passive"))
      (node (ref "S1_DIP8") (pin "3") (pinfunction "3_3") (pintype "bidirectional"))
    )
    (net (code "80") (name "Net-(JP4-Pad8)") (class "Default")
      (node (ref "JP4") (pin "8") (pinfunction "8_8") (pintype "passive"))
      (node (ref "R30") (pin "1") (pinfunction "1_1") (pintype "passive"))
      (node (ref "S1_DIP8") (pin "4") (pinfunction "4_4") (pintype "bidirectional"))
    )
    (net (code "81") (name "Net-(JP4-Pad10)") (class "Default")
      (node (ref "JP4") (pin "10") (pinfunction "10_10") (pintype "passive"))
      (node (ref "R29") (pin "1") (pinfunction "1_1") (pintype "passive"))
      (node (ref "S1_DIP8") (pin "5") (pinfunction "5_5") (pintype "bidirectional"))
    )
    (net (code "82") (name "Net-(JP4-Pad12)") (class "Default")
      (node (ref "JP4") (pin "12") (pinfunction "12_12") (pintype "passive"))
      (node (ref "R28") (pin "1") (pinfunction "1_1") (pintype "passive"))
      (node (ref "S1_DIP8") (pin "6") (pinfunction "6_6") (pintype "bidirectional"))
    )
    (net (code "83") (name "Net-(JP4-Pad14)") (class "Default")
      (node (ref "JP4") (pin "14") (pinfunction "14_14") (pintype "passive"))
      (node (ref "R27") (pin "1") (pinfunction "1_1") (pintype "passive"))
      (node (ref "S1_DIP8") (pin "7") (pinfunction "7_7") (pintype "bidirectional"))
    )
    (net (code "84") (name "Net-(JP4-Pad16)") (class "Default")
      (node (ref "JP4") (pin "16") (pinfunction "16_16") (pintype "passive"))
      (node (ref "R26") (pin "1") (pinfunction "1_1") (pintype "passive"))
      (node (ref "S1_DIP8") (pin "8") (pinfunction "8_8") (pintype "bidirectional"))
    )
    (net (code "85") (name "Net-(JP5-Pad3)") (class "Default")
      (node (ref "JP5") (pin "3") (pinfunction "3_3") (pintype "passive"))
      (node (ref "R59") (pin "1") (pinfunction "1_1") (pintype "passive"))
      (node (ref "S1") (pin "5") (pinfunction "5_5") (pintype "bidirectional"))
    )
    (net (code "86") (name "Net-(JP6-Pad1)") (class "Default")
      (node (ref "JP6") (pin "1") (pinfunction "1_1") (pintype "passive"))
      (node (ref "R58") (pin "1") (pinfunction "1_1") (pintype "passive"))
      (node (ref "S1") (pin "4") (pinfunction "4_4") (pintype "bidirectional"))
    )
    (net (code "87") (name "Net-(JP24-Pad3)") (class "Default")
      (node (ref "JP24") (pin "3") (pinfunction "3_3") (pintype "passive"))
      (node (ref "R60") (pin "1") (pinfunction "1_1") (pintype "passive"))
      (node (ref "S1") (pin "6") (pinfunction "6_6") (pintype "bidirectional"))
    )
    (net (code "88") (name "Net-(Q3-D)") (class "Default")
      (node (ref "D10") (pin "C") (pinfunction "C_C") (pintype "passive"))
      (node (ref "Q3") (pin "3") (pinfunction "D_3") (pintype "bidirectional"))
    )
    (net (code "89") (name "Net-(Q4-D)") (class "Default")
      (node (ref "D5") (pin "C") (pinfunction "C_C") (pintype "passive"))
      (node (ref "Q4") (pin "3") (pinfunction "D_3") (pintype "bidirectional"))
    )
    (net (code "90") (name "Net-(Q5-D)") (class "Default")
      (node (ref "D6") (pin "C") (pinfunction "C_C") (pintype "passive"))
      (node (ref "Q5") (pin "3") (pinfunction "D_3") (pintype "bidirectional"))
    )
    (net (code "91") (name "Net-(Q6-D)") (class "Default")
      (node (ref "D7") (pin "C") (pinfunction "C_C") (pintype "passive"))
      (node (ref "Q6") (pin "3") (pinfunction "D_3") (pintype "bidirectional"))
    )
    (net (code "92") (name "Net-(Q7-D)") (class "Default")
      (node (ref "D8") (pin "C") (pinfunction "C_C") (pintype "passive"))
      (node (ref "Q7") (pin "3") (pinfunction "D_3") (pintype "bidirectional"))
    )
    (net (code "93") (name "Net-(Q8-D)") (class "Default")
      (node (ref "D9") (pin "C") (pinfunction "C_C") (pintype "passive"))
      (node (ref "Q8") (pin "3") (pinfunction "D_3") (pintype "bidirectional"))
    )
    (net (code "94") (name "Net-(Q9-D)") (class "Default")
      (node (ref "D11") (pin "C") (pinfunction "C_C") (pintype "passive"))
      (node (ref "Q9") (pin "3") (pinfunction "D_3") (pintype "bidirectional"))
    )
    (net (code "95") (name "Net-(Q10-D)") (class "Default")
      (node (ref "D12") (pin "C") (pinfunction "C_C") (pintype "passive"))
      (node (ref "Q10") (pin "3") (pinfunction "D_3") (pintype "bidirectional"))
    )
    (net (code "96") (name "Net-(Q11-D)") (class "Default")
      (node (ref "D13") (pin "C") (pinfunction "C_C") (pintype "passive"))
      (node (ref "Q11") (pin "3") (pinfunction "D_3") (pintype "bidirectional"))
    )
    (net (code "97") (name "Net-(Q12-D)") (class "Default")
      (node (ref "D14") (pin "C") (pinfunction "C_C") (pintype "passive"))
      (node (ref "Q12") (pin "3") (pinfunction "D_3") (pintype "bidirectional"))
    )
    (net (code "98") (name "Net-(Q13-D)") (class "Default")
      (node (ref "D15") (pin "C") (pinfunction "C_C") (pintype "passive"))
      (node (ref "Q13") (pin "3") (pinfunction "D_3") (pintype "bidirectional"))
    )
    (net (code "99") (name "QSPI_CS") (class "Default")
      (node (ref "JP2") (pin "1") (pinfunction "1_1") (pintype "passive"))
      (node (ref "SOCKET_2") (pin "7") (pinfunction "7_7") (pintype "passive"))
    )
    (net (code "100") (name "QSPI_MISO") (class "Default")
      (node (ref "JP2") (pin "3") (pinfunction "3_3") (pintype "passive"))
      (node (ref "SOCKET_2") (pin "10") (pinfunction "10_10") (pintype "passive"))
    )
    (net (code "101") (name "QSPI_MOSI") (class "Default")
      (node (ref "JP2") (pin "5") (pinfunction "5_5") (pintype "passive"))
      (node (ref "SOCKET_2") (pin "11") (pinfunction "11_11") (pintype "passive"))
    )
    (net (code "102") (name "QSPI_SCK") (class "Default")
      (node (ref "JP2") (pin "7") (pinfunction "7_7") (pintype "passive"))
      (node (ref "SOCKET_2") (pin "9") (pinfunction "9_9") (pintype "passive"))
    )
    (net (code "103") (name "RST_N") (class "Default")
      (node (ref "JP5") (pin "2") (pinfunction "2_2") (pintype "passive"))
      (node (ref "JP5") (pin "4") (pinfunction "4_4") (pintype "passive"))
      (node (ref "SOCKET_2") (pin "15") (pinfunction "15_15") (pintype "passive"))
    )
    (net (code "104") (name "RST_N_GPIO") (class "Default")
      (node (ref "JP18") (pin "2") (pinfunction "2_2") (pintype "passive"))
      (node (ref "JP5") (pin "1") (pinfunction "1_1") (pintype "passive"))
    )
    (net (code "105") (name "SDIO_CLK") (class "Default")
      (node (ref "JP1") (pin "5") (pinfunction "5_5") (pintype "passive"))
      (node (ref "SOCKET_1") (pin "31") (pinfunction "31_31") (pintype "passive"))
    )
    (net (code "106") (name "SDIO_CMD") (class "Default")
      (node (ref "JP1") (pin "3") (pinfunction "3_3") (pintype "passive"))
      (node (ref "SOCKET_1") (pin "32") (pinfunction "32_32") (pintype "passive"))
    )
    (net (code "107") (name "SDIO_DAT_0") (class "Default")
      (node (ref "JP1") (pin "7") (pinfunction "7_7") (pintype "passive"))
      (node (ref "SOCKET_2") (pin "1") (pinfunction "1_1") (pintype "passive"))
    )
    (net (code "108") (name "SDIO_DAT_3") (class "Default")
      (node (ref "JP1") (pin "1") (pinfunction "1_1") (pintype "passive"))
      (node (ref "SOCKET_2") (pin "2") (pinfunction "2_2") (pintype "passive"))
    )
    (net (code "109") (name "SYS_CLK") (class "Default")
      (node (ref "J4") (pin "5") (pinfunction "5_5") (pintype "bidirectional"))
      (node (ref "SOCKET_2") (pin "14") (pinfunction "14_14") (pintype "passive"))
    )
    (net (code "110") (name "TCK") (class "Default")
      (node (ref "IC4") (pin "12") (pinfunction "B3_12") (pintype "bidirectional"))
      (node (ref "JTAG_20_PIN") (pin "9") (pinfunction "9_9") (pintype "passive"))
      (node (ref "R24") (pin "1") (pinfunction "1_1") (pintype "passive"))
    )
    (net (code "111") (name "TDI") (class "Default")
      (node (ref "IC4") (pin "14") (pinfunction "B1_14") (pintype "bidirectional"))
      (node (ref "JTAG_20_PIN") (pin "5") (pinfunction "5_5") (pintype "passive"))
      (node (ref "R23") (pin "1") (pinfunction "1_1") (pintype "passive"))
    )
    (net (code "112") (name "TDO") (class "Default")
      (node (ref "IC4") (pin "11") (pinfunction "B4_11") (pintype "bidirectional"))
      (node (ref "JTAG_20_PIN") (pin "13") (pinfunction "13_13") (pintype "passive"))
      (node (ref "R25") (pin "1") (pinfunction "1_1") (pintype "passive"))
    )
    (net (code "113") (name "TLPORT_A_BITS_ADDRESS[0]") (class "Default")
      (node (ref "JP19") (pin "18") (pinfunction "18_18") (pintype "passive"))
      (node (ref "SOCKET_4") (pin "23") (pinfunction "23_23") (pintype "passive"))
    )
    (net (code "114") (name "TLPORT_A_BITS_ADDRESS[1]") (class "Default")
      (node (ref "JP19") (pin "17") (pinfunction "17_17") (pintype "passive"))
      (node (ref "SOCKET_4") (pin "21") (pinfunction "21_21") (pintype "passive"))
    )
    (net (code "115") (name "TLPORT_A_BITS_ADDRESS[2]") (class "Default")
      (node (ref "JP19") (pin "16") (pinfunction "16_16") (pintype "passive"))
      (node (ref "SOCKET_4") (pin "20") (pinfunction "20_20") (pintype "passive"))
    )
    (net (code "116") (name "TLPORT_A_BITS_ADDRESS[3]") (class "Default")
      (node (ref "JP19") (pin "15") (pinfunction "15_15") (pintype "passive"))
      (node (ref "SOCKET_4") (pin "18") (pinfunction "18_18") (pintype "passive"))
    )
    (net (code "117") (name "TLPORT_A_BITS_ADDRESS[4]") (class "Default")
      (node (ref "JP19") (pin "14") (pinfunction "14_14") (pintype "passive"))
      (node (ref "SOCKET_4") (pin "17") (pinfunction "17_17") (pintype "passive"))
    )
    (net (code "118") (name "TLPORT_A_BITS_ADDRESS[5]") (class "Default")
      (node (ref "JP19") (pin "13") (pinfunction "13_13") (pintype "passive"))
      (node (ref "SOCKET_4") (pin "15") (pinfunction "15_15") (pintype "passive"))
    )
    (net (code "119") (name "TLPORT_A_BITS_ADDRESS[6]") (class "Default")
      (node (ref "JP19") (pin "10") (pinfunction "10_10") (pintype "passive"))
      (node (ref "SOCKET_4") (pin "14") (pinfunction "14_14") (pintype "passive"))
    )
    (net (code "120") (name "TLPORT_A_BITS_ADDRESS[7]") (class "Default")
      (node (ref "JP19") (pin "9") (pinfunction "9_9") (pintype "passive"))
      (node (ref "SOCKET_4") (pin "13") (pinfunction "13_13") (pintype "passive"))
    )
    (net (code "121") (name "TLPORT_A_BITS_ADDRESS[8]") (class "Default")
      (node (ref "JP19") (pin "8") (pinfunction "8_8") (pintype "passive"))
      (node (ref "SOCKET_4") (pin "12") (pinfunction "12_12") (pintype "passive"))
    )
    (net (code "122") (name "TLPORT_A_BITS_ADDRESS[9]") (class "Default")
      (node (ref "JP19") (pin "7") (pinfunction "7_7") (pintype "passive"))
      (node (ref "SOCKET_4") (pin "11") (pinfunction "11_11") (pintype "passive"))
    )
    (net (code "123") (name "TLPORT_A_BITS_ADDRESS[10]") (class "Default")
      (node (ref "JP19") (pin "6") (pinfunction "6_6") (pintype "passive"))
      (node (ref "SOCKET_4") (pin "10") (pinfunction "10_10") (pintype "passive"))
    )
    (net (code "124") (name "TLPORT_A_BITS_ADDRESS[11]") (class "Default")
      (node (ref "JP19") (pin "5") (pinfunction "5_5") (pintype "passive"))
      (node (ref "SOCKET_4") (pin "9") (pinfunction "9_9") (pintype "passive"))
    )
    (net (code "125") (name "TLPORT_A_BITS_ADDRESS[12]") (class "Default")
      (node (ref "JP19") (pin "4") (pinfunction "4_4") (pintype "passive"))
      (node (ref "SOCKET_4") (pin "7") (pinfunction "7_7") (pintype "passive"))
    )
    (net (code "126") (name "TLPORT_A_BITS_ADDRESS[13]") (class "Default")
      (node (ref "JP19") (pin "3") (pinfunction "3_3") (pintype "passive"))
      (node (ref "SOCKET_4") (pin "6") (pinfunction "6_6") (pintype "passive"))
    )
    (net (code "127") (name "TLPORT_A_BITS_ADDRESS[14]") (class "Default")
      (node (ref "JP19") (pin "2") (pinfunction "2_2") (pintype "passive"))
      (node (ref "SOCKET_4") (pin "5") (pinfunction "5_5") (pintype "passive"))
    )
    (net (code "128") (name "TLPORT_A_BITS_ADDRESS[15]") (class "Default")
      (node (ref "JP19") (pin "1") (pinfunction "1_1") (pintype "passive"))
      (node (ref "SOCKET_4") (pin "4") (pinfunction "4_4") (pintype "passive"))
    )
    (net (code "129") (name "TLPORT_A_BITS_ADDRESS[16]") (class "Default")
      (node (ref "JP18") (pin "40") (pinfunction "40_40") (pintype "passive"))
      (node (ref "SOCKET_4") (pin "3") (pinfunction "3_3") (pintype "passive"))
    )
    (net (code "130") (name "TLPORT_A_BITS_ADDRESS[17]") (class "Default")
      (node (ref "JP18") (pin "39") (pinfunction "39_39") (pintype "passive"))
      (node (ref "SOCKET_4") (pin "2") (pinfunction "2_2") (pintype "passive"))
    )
    (net (code "131") (name "TLPORT_A_BITS_ADDRESS[18]") (class "Default")
      (node (ref "JP18") (pin "38") (pinfunction "38_38") (pintype "passive"))
      (node (ref "SOCKET_4") (pin "1") (pinfunction "1_1") (pintype "passive"))
    )
    (net (code "132") (name "TLPORT_A_BITS_ADDRESS[19]") (class "Default")
      (node (ref "JP18") (pin "37") (pinfunction "37_37") (pintype "passive"))
      (node (ref "SOCKET_3") (pin "32") (pinfunction "32_32") (pintype "passive"))
    )
    (net (code "133") (name "TLPORT_A_BITS_ADDRESS[20]") (class "Default")
      (node (ref "JP18") (pin "36") (pinfunction "36_36") (pintype "passive"))
      (node (ref "SOCKET_3") (pin "31") (pinfunction "31_31") (pintype "passive"))
    )
    (net (code "134") (name "TLPORT_A_BITS_ADDRESS[21]") (class "Default")
      (node (ref "JP18") (pin "35") (pinfunction "35_35") (pintype "passive"))
      (node (ref "SOCKET_3") (pin "29") (pinfunction "29_29") (pintype "passive"))
    )
    (net (code "135") (name "TLPORT_A_BITS_ADDRESS[22]") (class "Default")
      (node (ref "JP18") (pin "34") (pinfunction "34_34") (pintype "passive"))
      (node (ref "SOCKET_3") (pin "28") (pinfunction "28_28") (pintype "passive"))
    )
    (net (code "136") (name "TLPORT_A_BITS_ADDRESS[23]") (class "Default")
      (node (ref "JP18") (pin "33") (pinfunction "33_33") (pintype "passive"))
      (node (ref "SOCKET_3") (pin "27") (pinfunction "27_27") (pintype "passive"))
    )
    (net (code "137") (name "TLPORT_A_BITS_ADDRESS[24]") (class "Default")
      (node (ref "JP18") (pin "32") (pinfunction "32_32") (pintype "passive"))
      (node (ref "SOCKET_3") (pin "26") (pinfunction "26_26") (pintype "passive"))
    )
    (net (code "138") (name "TLPORT_A_BITS_ADDRESS[25]") (class "Default")
      (node (ref "JP18") (pin "31") (pinfunction "31_31") (pintype "passive"))
      (node (ref "SOCKET_3") (pin "25") (pinfunction "25_25") (pintype "passive"))
    )
    (net (code "139") (name "TLPORT_A_BITS_ADDRESS[26]") (class "Default")
      (node (ref "JP18") (pin "28") (pinfunction "28_28") (pintype "passive"))
      (node (ref "SOCKET_3") (pin "23") (pinfunction "23_23") (pintype "passive"))
    )
    (net (code "140") (name "TLPORT_A_BITS_ADDRESS[27]") (class "Default")
      (node (ref "JP18") (pin "27") (pinfunction "27_27") (pintype "passive"))
      (node (ref "SOCKET_3") (pin "22") (pinfunction "22_22") (pintype "passive"))
    )
    (net (code "141") (name "TLPORT_A_BITS_ADDRESS[28]") (class "Default")
      (node (ref "JP18") (pin "26") (pinfunction "26_26") (pintype "passive"))
      (node (ref "SOCKET_3") (pin "21") (pinfunction "21_21") (pintype "passive"))
    )
    (net (code "142") (name "TLPORT_A_BITS_ADDRESS[29]") (class "Default")
      (node (ref "JP18") (pin "25") (pinfunction "25_25") (pintype "passive"))
      (node (ref "SOCKET_3") (pin "20") (pinfunction "20_20") (pintype "passive"))
    )
    (net (code "143") (name "TLPORT_A_BITS_ADDRESS[30]") (class "Default")
      (node (ref "JP18") (pin "24") (pinfunction "24_24") (pintype "passive"))
      (node (ref "SOCKET_3") (pin "19") (pinfunction "19_19") (pintype "passive"))
    )
    (net (code "144") (name "TLPORT_A_BITS_ADDRESS[31]") (class "Default")
      (node (ref "JP18") (pin "23") (pinfunction "23_23") (pintype "passive"))
      (node (ref "SOCKET_3") (pin "18") (pinfunction "18_18") (pintype "passive"))
    )
    (net (code "145") (name "TLPORT_A_BITS_CORRUPT") (class "Default")
      (node (ref "JP20") (pin "19") (pinfunction "19_19") (pintype "passive"))
      (node (ref "SOCKET_6") (pin "14") (pinfunction "14_14") (pintype "passive"))
    )
    (net (code "146") (name "TLPORT_A_BITS_DATA[0]") (class "Default")
      (node (ref "JP20") (pin "18") (pinfunction "18_18") (pintype "passive"))
      (node (ref "SOCKET_6") (pin "13") (pinfunction "13_13") (pintype "passive"))
    )
    (net (code "147") (name "TLPORT_A_BITS_DATA[1]") (class "Default")
      (node (ref "JP20") (pin "17") (pinfunction "17_17") (pintype "passive"))
      (node (ref "SOCKET_6") (pin "12") (pinfunction "12_12") (pintype "passive"))
    )
    (net (code "148") (name "TLPORT_A_BITS_DATA[2]") (class "Default")
      (node (ref "JP20") (pin "16") (pinfunction "16_16") (pintype "passive"))
      (node (ref "SOCKET_6") (pin "11") (pinfunction "11_11") (pintype "passive"))
    )
    (net (code "149") (name "TLPORT_A_BITS_DATA[3]") (class "Default")
      (node (ref "JP20") (pin "15") (pinfunction "15_15") (pintype "passive"))
      (node (ref "SOCKET_6") (pin "10") (pinfunction "10_10") (pintype "passive"))
    )
    (net (code "150") (name "TLPORT_A_BITS_DATA[4]") (class "Default")
      (node (ref "JP20") (pin "14") (pinfunction "14_14") (pintype "passive"))
      (node (ref "SOCKET_6") (pin "9") (pinfunction "9_9") (pintype "passive"))
    )
    (net (code "151") (name "TLPORT_A_BITS_DATA[5]") (class "Default")
      (node (ref "JP20") (pin "13") (pinfunction "13_13") (pintype "passive"))
      (node (ref "SOCKET_6") (pin "7") (pinfunction "7_7") (pintype "passive"))
    )
    (net (code "152") (name "TLPORT_A_BITS_DATA[6]") (class "Default")
      (node (ref "JP20") (pin "1") (pinfunction "1_1") (pintype "passive"))
      (node (ref "SOCKET_6") (pin "6") (pinfunction "6_6") (pintype "passive"))
    )
    (net (code "153") (name "TLPORT_A_BITS_DATA[7]") (class "Default")
      (node (ref "JP20") (pin "2") (pinfunction "2_2") (pintype "passive"))
      (node (ref "SOCKET_6") (pin "5") (pinfunction "5_5") (pintype "passive"))
    )
    (net (code "154") (name "TLPORT_A_BITS_DATA[8]") (class "Default")
      (node (ref "JP20") (pin "3") (pinfunction "3_3") (pintype "passive"))
      (node (ref "SOCKET_6") (pin "4") (pinfunction "4_4") (pintype "passive"))
    )
    (net (code "155") (name "TLPORT_A_BITS_DATA[9]") (class "Default")
      (node (ref "JP20") (pin "4") (pinfunction "4_4") (pintype "passive"))
      (node (ref "SOCKET_6") (pin "3") (pinfunction "3_3") (pintype "passive"))
    )
    (net (code "156") (name "TLPORT_A_BITS_DATA[10]") (class "Default")
      (node (ref "JP20") (pin "5") (pinfunction "5_5") (pintype "passive"))
      (node (ref "SOCKET_6") (pin "2") (pinfunction "2_2") (pintype "passive"))
    )
    (net (code "157") (name "TLPORT_A_BITS_DATA[11]") (class "Default")
      (node (ref "JP20") (pin "6") (pinfunction "6_6") (pintype "passive"))
      (node (ref "SOCKET_6") (pin "1") (pinfunction "1_1") (pintype "passive"))
    )
    (net (code "158") (name "TLPORT_A_BITS_DATA[12]") (class "Default")
      (node (ref "JP20") (pin "7") (pinfunction "7_7") (pintype "passive"))
      (node (ref "SOCKET_5") (pin "32") (pinfunction "32_32") (pintype "passive"))
    )
    (net (code "159") (name "TLPORT_A_BITS_DATA[13]") (class "Default")
      (node (ref "JP20") (pin "8") (pinfunction "8_8") (pintype "passive"))
      (node (ref "SOCKET_5") (pin "31") (pinfunction "31_31") (pintype "passive"))
    )
    (net (code "160") (name "TLPORT_A_BITS_DATA[14]") (class "Default")
      (node (ref "JP20") (pin "9") (pinfunction "9_9") (pintype "passive"))
      (node (ref "SOCKET_5") (pin "29") (pinfunction "29_29") (pintype "passive"))
    )
    (net (code "161") (name "TLPORT_A_BITS_DATA[15]") (class "Default")
      (node (ref "JP20") (pin "10") (pinfunction "10_10") (pintype "passive"))
      (node (ref "SOCKET_5") (pin "28") (pinfunction "28_28") (pintype "passive"))
    )
    (net (code "162") (name "TLPORT_A_BITS_DATA[16]") (class "Default")
      (node (ref "JP19") (pin "31") (pinfunction "31_31") (pintype "passive"))
      (node (ref "SOCKET_5") (pin "27") (pinfunction "27_27") (pintype "passive"))
    )
    (net (code "163") (name "TLPORT_A_BITS_DATA[17]") (class "Default")
      (node (ref "JP19") (pin "32") (pinfunction "32_32") (pintype "passive"))
      (node (ref "SOCKET_5") (pin "26") (pinfunction "26_26") (pintype "passive"))
    )
    (net (code "164") (name "TLPORT_A_BITS_DATA[18]") (class "Default")
      (node (ref "JP19") (pin "33") (pinfunction "33_33") (pintype "passive"))
      (node (ref "SOCKET_5") (pin "25") (pinfunction "25_25") (pintype "passive"))
    )
    (net (code "165") (name "TLPORT_A_BITS_DATA[19]") (class "Default")
      (node (ref "JP19") (pin "34") (pinfunction "34_34") (pintype "passive"))
      (node (ref "SOCKET_5") (pin "23") (pinfunction "23_23") (pintype "passive"))
    )
    (net (code "166") (name "TLPORT_A_BITS_DATA[20]") (class "Default")
      (node (ref "JP19") (pin "35") (pinfunction "35_35") (pintype "passive"))
      (node (ref "SOCKET_5") (pin "22") (pinfunction "22_22") (pintype "passive"))
    )
    (net (code "167") (name "TLPORT_A_BITS_DATA[21]") (class "Default")
      (node (ref "JP19") (pin "36") (pinfunction "36_36") (pintype "passive"))
      (node (ref "SOCKET_5") (pin "21") (pinfunction "21_21") (pintype "passive"))
    )
    (net (code "168") (name "TLPORT_A_BITS_DATA[22]") (class "Default")
      (node (ref "JP19") (pin "37") (pinfunction "37_37") (pintype "passive"))
      (node (ref "SOCKET_5") (pin "20") (pinfunction "20_20") (pintype "passive"))
    )
    (net (code "169") (name "TLPORT_A_BITS_DATA[23]") (class "Default")
      (node (ref "JP19") (pin "38") (pinfunction "38_38") (pintype "passive"))
      (node (ref "SOCKET_5") (pin "19") (pinfunction "19_19") (pintype "passive"))
    )
    (net (code "170") (name "TLPORT_A_BITS_DATA[24]") (class "Default")
      (node (ref "JP19") (pin "39") (pinfunction "39_39") (pintype "passive"))
      (node (ref "SOCKET_5") (pin "18") (pinfunction "18_18") (pintype "passive"))
    )
    (net (code "171") (name "TLPORT_A_BITS_DATA[25]") (class "Default")
      (node (ref "JP19") (pin "40") (pinfunction "40_40") (pintype "passive"))
      (node (ref "SOCKET_5") (pin "17") (pinfunction "17_17") (pintype "passive"))
    )
    (net (code "172") (name "TLPORT_A_BITS_DATA[26]") (class "Default")
      (node (ref "JP19") (pin "28") (pinfunction "28_28") (pintype "passive"))
      (node (ref "SOCKET_5") (pin "15") (pinfunction "15_15") (pintype "passive"))
    )
    (net (code "173") (name "TLPORT_A_BITS_DATA[27]") (class "Default")
      (node (ref "JP19") (pin "27") (pinfunction "27_27") (pintype "passive"))
      (node (ref "SOCKET_5") (pin "14") (pinfunction "14_14") (pintype "passive"))
    )
    (net (code "174") (name "TLPORT_A_BITS_DATA[28]") (class "Default")
      (node (ref "JP19") (pin "26") (pinfunction "26_26") (pintype "passive"))
      (node (ref "SOCKET_5") (pin "13") (pinfunction "13_13") (pintype "passive"))
    )
    (net (code "175") (name "TLPORT_A_BITS_DATA[29]") (class "Default")
      (node (ref "JP19") (pin "25") (pinfunction "25_25") (pintype "passive"))
      (node (ref "SOCKET_5") (pin "12") (pinfunction "12_12") (pintype "passive"))
    )
    (net (code "176") (name "TLPORT_A_BITS_DATA[30]") (class "Default")
      (node (ref "JP19") (pin "24") (pinfunction "24_24") (pintype "passive"))
      (node (ref "SOCKET_5") (pin "10") (pinfunction "10_10") (pintype "passive"))
    )
    (net (code "177") (name "TLPORT_A_BITS_DATA[31]") (class "Default")
      (node (ref "JP19") (pin "23") (pinfunction "23_23") (pintype "passive"))
      (node (ref "SOCKET_5") (pin "9") (pinfunction "9_9") (pintype "passive"))
    )
    (net (code "178") (name "TLPORT_A_BITS_MASK[0]") (class "Default")
      (node (ref "JP19") (pin "22") (pinfunction "22_22") (pintype "passive"))
      (node (ref "SOCKET_5") (pin "8") (pinfunction "8_8") (pintype "passive"))
    )
    (net (code "179") (name "TLPORT_A_BITS_MASK[1]") (class "Default")
      (node (ref "JP19") (pin "21") (pinfunction "21_21") (pintype "passive"))
      (node (ref "SOCKET_5") (pin "7") (pinfunction "7_7") (pintype "passive"))
    )
    (net (code "180") (name "TLPORT_A_BITS_MASK[2]") (class "Default")
      (node (ref "JP19") (pin "20") (pinfunction "20_20") (pintype "passive"))
      (node (ref "SOCKET_4") (pin "25") (pinfunction "25_25") (pintype "passive"))
    )
    (net (code "181") (name "TLPORT_A_BITS_MASK[3]") (class "Default")
      (node (ref "JP19") (pin "19") (pinfunction "19_19") (pintype "passive"))
      (node (ref "SOCKET_4") (pin "24") (pinfunction "24_24") (pintype "passive"))
    )
    (net (code "182") (name "TLPORT_A_BITS_OPCODE[0]") (class "Default")
      (node (ref "JP18") (pin "8") (pinfunction "8_8") (pintype "passive"))
      (node (ref "SOCKET_2") (pin "24") (pinfunction "24_24") (pintype "passive"))
    )
    (net (code "183") (name "TLPORT_A_BITS_OPCODE[1]") (class "Default")
      (node (ref "JP18") (pin "7") (pinfunction "7_7") (pintype "passive"))
      (node (ref "SOCKET_2") (pin "23") (pinfunction "23_23") (pintype "passive"))
    )
    (net (code "184") (name "TLPORT_A_BITS_OPCODE[2]") (class "Default")
      (node (ref "JP18") (pin "3") (pinfunction "3_3") (pintype "passive"))
      (node (ref "SOCKET_2") (pin "21") (pinfunction "21_21") (pintype "passive"))
    )
    (net (code "185") (name "TLPORT_A_BITS_PARAM[0]") (class "Default")
      (node (ref "JP18") (pin "13") (pinfunction "13_13") (pintype "passive"))
      (node (ref "SOCKET_2") (pin "27") (pinfunction "27_27") (pintype "passive"))
    )
    (net (code "186") (name "TLPORT_A_BITS_PARAM[1]") (class "Default")
      (node (ref "JP18") (pin "10") (pinfunction "10_10") (pintype "passive"))
      (node (ref "SOCKET_2") (pin "26") (pinfunction "26_26") (pintype "passive"))
    )
    (net (code "187") (name "TLPORT_A_BITS_PARAM[2]") (class "Default")
      (node (ref "JP18") (pin "9") (pinfunction "9_9") (pintype "passive"))
      (node (ref "SOCKET_2") (pin "25") (pinfunction "25_25") (pintype "passive"))
    )
    (net (code "188") (name "TLPORT_A_BITS_SIZE[0]") (class "Default")
      (node (ref "JP18") (pin "16") (pinfunction "16_16") (pintype "passive"))
      (node (ref "SOCKET_3") (pin "9") (pinfunction "9_9") (pintype "passive"))
    )
    (net (code "189") (name "TLPORT_A_BITS_SIZE[1]") (class "Default")
      (node (ref "JP18") (pin "15") (pinfunction "15_15") (pintype "passive"))
      (node (ref "SOCKET_3") (pin "8") (pinfunction "8_8") (pintype "passive"))
    )
    (net (code "190") (name "TLPORT_A_BITS_SIZE[2]") (class "Default")
      (node (ref "JP18") (pin "14") (pinfunction "14_14") (pintype "passive"))
      (node (ref "SOCKET_3") (pin "7") (pinfunction "7_7") (pintype "passive"))
    )
    (net (code "191") (name "TLPORT_A_BITS_SOURCE[0]") (class "Default")
      (node (ref "JP18") (pin "22") (pinfunction "22_22") (pintype "passive"))
      (node (ref "SOCKET_3") (pin "17") (pinfunction "17_17") (pintype "passive"))
    )
    (net (code "192") (name "TLPORT_A_BITS_SOURCE[1]") (class "Default")
      (node (ref "JP18") (pin "21") (pinfunction "21_21") (pintype "passive"))
      (node (ref "SOCKET_3") (pin "15") (pinfunction "15_15") (pintype "passive"))
    )
    (net (code "193") (name "TLPORT_A_BITS_SOURCE[2]") (class "Default")
      (node (ref "JP18") (pin "20") (pinfunction "20_20") (pintype "passive"))
      (node (ref "SOCKET_3") (pin "14") (pinfunction "14_14") (pintype "passive"))
    )
    (net (code "194") (name "TLPORT_A_BITS_SOURCE[3]") (class "Default")
      (node (ref "JP18") (pin "19") (pinfunction "19_19") (pintype "passive"))
      (node (ref "SOCKET_3") (pin "13") (pinfunction "13_13") (pintype "passive"))
    )
    (net (code "195") (name "TLPORT_A_BITS_SOURCE[4]") (class "Default")
      (node (ref "JP18") (pin "18") (pinfunction "18_18") (pintype "passive"))
      (node (ref "SOCKET_3") (pin "12") (pinfunction "12_12") (pintype "passive"))
    )
    (net (code "196") (name "TLPORT_A_BITS_SOURCE[5]") (class "Default")
      (node (ref "JP18") (pin "17") (pinfunction "17_17") (pintype "passive"))
      (node (ref "SOCKET_3") (pin "10") (pinfunction "10_10") (pintype "passive"))
    )
    (net (code "197") (name "TLPORT_A_READY") (class "Default")
      (node (ref "JP18") (pin "4") (pinfunction "4_4") (pintype "passive"))
      (node (ref "SOCKET_2") (pin "18") (pinfunction "18_18") (pintype "passive"))
    )
    (net (code "198") (name "TLPORT_A_VALID") (class "Default")
      (node (ref "JP18") (pin "1") (pinfunction "1_1") (pintype "passive"))
      (node (ref "SOCKET_2") (pin "20") (pinfunction "20_20") (pintype "passive"))
    )
    (net (code "199") (name "TLPORT_D_BITS_CORRUPT") (class "Default")
      (node (ref "JP20") (pin "40") (pinfunction "40_40") (pintype "passive"))
      (node (ref "SOCKET_7") (pin "19") (pinfunction "19_19") (pintype "passive"))
    )
    (net (code "200") (name "TLPORT_D_BITS_DATA[0]") (class "Default")
      (node (ref "JP21") (pin "40") (pinfunction "40_40") (pintype "passive"))
      (node (ref "SOCKET_8") (pin "25") (pinfunction "25_25") (pintype "passive"))
    )
    (net (code "201") (name "TLPORT_D_BITS_DATA[1]") (class "Default")
      (node (ref "JP21") (pin "39") (pinfunction "39_39") (pintype "passive"))
      (node (ref "SOCKET_8") (pin "24") (pinfunction "24_24") (pintype "passive"))
    )
    (net (code "202") (name "TLPORT_D_BITS_DATA[2]") (class "Default")
      (node (ref "JP21") (pin "38") (pinfunction "38_38") (pintype "passive"))
      (node (ref "SOCKET_8") (pin "23") (pinfunction "23_23") (pintype "passive"))
    )
    (net (code "203") (name "TLPORT_D_BITS_DATA[3]") (class "Default")
      (node (ref "JP21") (pin "37") (pinfunction "37_37") (pintype "passive"))
      (node (ref "SOCKET_8") (pin "21") (pinfunction "21_21") (pintype "passive"))
    )
    (net (code "204") (name "TLPORT_D_BITS_DATA[4]") (class "Default")
      (node (ref "JP21") (pin "36") (pinfunction "36_36") (pintype "passive"))
      (node (ref "SOCKET_8") (pin "20") (pinfunction "20_20") (pintype "passive"))
    )
    (net (code "205") (name "TLPORT_D_BITS_DATA[5]") (class "Default")
      (node (ref "JP21") (pin "35") (pinfunction "35_35") (pintype "passive"))
      (node (ref "SOCKET_8") (pin "18") (pinfunction "18_18") (pintype "passive"))
    )
    (net (code "206") (name "TLPORT_D_BITS_DATA[6]") (class "Default")
      (node (ref "JP21") (pin "34") (pinfunction "34_34") (pintype "passive"))
      (node (ref "SOCKET_8") (pin "17") (pinfunction "17_17") (pintype "passive"))
    )
    (net (code "207") (name "TLPORT_D_BITS_DATA[7]") (class "Default")
      (node (ref "JP21") (pin "33") (pinfunction "33_33") (pintype "passive"))
      (node (ref "SOCKET_8") (pin "15") (pinfunction "15_15") (pintype "passive"))
    )
    (net (code "208") (name "TLPORT_D_BITS_DATA[8]") (class "Default")
      (node (ref "JP21") (pin "32") (pinfunction "32_32") (pintype "passive"))
      (node (ref "SOCKET_8") (pin "14") (pinfunction "14_14") (pintype "passive"))
    )
    (net (code "209") (name "TLPORT_D_BITS_DATA[9]") (class "Default")
      (node (ref "JP21") (pin "31") (pinfunction "31_31") (pintype "passive"))
      (node (ref "SOCKET_8") (pin "13") (pinfunction "13_13") (pintype "passive"))
    )
    (net (code "210") (name "TLPORT_D_BITS_DATA[10]") (class "Default")
      (node (ref "JP21") (pin "28") (pinfunction "28_28") (pintype "passive"))
      (node (ref "SOCKET_8") (pin "12") (pinfunction "12_12") (pintype "passive"))
    )
    (net (code "211") (name "TLPORT_D_BITS_DATA[11]") (class "Default")
      (node (ref "JP21") (pin "27") (pinfunction "27_27") (pintype "passive"))
      (node (ref "SOCKET_8") (pin "11") (pinfunction "11_11") (pintype "passive"))
    )
    (net (code "212") (name "TLPORT_D_BITS_DATA[12]") (class "Default")
      (node (ref "JP21") (pin "26") (pinfunction "26_26") (pintype "passive"))
      (node (ref "SOCKET_8") (pin "10") (pinfunction "10_10") (pintype "passive"))
    )
    (net (code "213") (name "TLPORT_D_BITS_DATA[13]") (class "Default")
      (node (ref "JP21") (pin "25") (pinfunction "25_25") (pintype "passive"))
      (node (ref "SOCKET_8") (pin "9") (pinfunction "9_9") (pintype "passive"))
    )
    (net (code "214") (name "TLPORT_D_BITS_DATA[14]") (class "Default")
      (node (ref "JP21") (pin "24") (pinfunction "24_24") (pintype "passive"))
      (node (ref "SOCKET_8") (pin "7") (pinfunction "7_7") (pintype "passive"))
    )
    (net (code "215") (name "TLPORT_D_BITS_DATA[15]") (class "Default")
      (node (ref "JP21") (pin "23") (pinfunction "23_23") (pintype "passive"))
      (node (ref "SOCKET_8") (pin "6") (pinfunction "6_6") (pintype "passive"))
    )
    (net (code "216") (name "TLPORT_D_BITS_DATA[16]") (class "Default")
      (node (ref "JP21") (pin "22") (pinfunction "22_22") (pintype "passive"))
      (node (ref "SOCKET_8") (pin "5") (pinfunction "5_5") (pintype "passive"))
    )
    (net (code "217") (name "TLPORT_D_BITS_DATA[17]") (class "Default")
      (node (ref "JP21") (pin "21") (pinfunction "21_21") (pintype "passive"))
      (node (ref "SOCKET_8") (pin "4") (pinfunction "4_4") (pintype "passive"))
    )
    (net (code "218") (name "TLPORT_D_BITS_DATA[18]") (class "Default")
      (node (ref "JP21") (pin "20") (pinfunction "20_20") (pintype "passive"))
      (node (ref "SOCKET_8") (pin "3") (pinfunction "3_3") (pintype "passive"))
    )
    (net (code "219") (name "TLPORT_D_BITS_DATA[19]") (class "Default")
      (node (ref "JP21") (pin "19") (pinfunction "19_19") (pintype "passive"))
      (node (ref "SOCKET_8") (pin "2") (pinfunction "2_2") (pintype "passive"))
    )
    (net (code "220") (name "TLPORT_D_BITS_DATA[20]") (class "Default")
      (node (ref "JP21") (pin "18") (pinfunction "18_18") (pintype "passive"))
      (node (ref "SOCKET_8") (pin "1") (pinfunction "1_1") (pintype "passive"))
    )
    (net (code "221") (name "TLPORT_D_BITS_DATA[21]") (class "Default")
      (node (ref "JP21") (pin "17") (pinfunction "17_17") (pintype "passive"))
      (node (ref "SOCKET_7") (pin "32") (pinfunction "32_32") (pintype "passive"))
    )
    (net (code "222") (name "TLPORT_D_BITS_DATA[22]") (class "Default")
      (node (ref "JP21") (pin "16") (pinfunction "16_16") (pintype "passive"))
      (node (ref "SOCKET_7") (pin "31") (pinfunction "31_31") (pintype "passive"))
    )
    (net (code "223") (name "TLPORT_D_BITS_DATA[23]") (class "Default")
      (node (ref "JP21") (pin "15") (pinfunction "15_15") (pintype "passive"))
      (node (ref "SOCKET_7") (pin "29") (pinfunction "29_29") (pintype "passive"))
    )
    (net (code "224") (name "TLPORT_D_BITS_DATA[24]") (class "Default")
      (node (ref "JP21") (pin "14") (pinfunction "14_14") (pintype "passive"))
      (node (ref "SOCKET_7") (pin "28") (pinfunction "28_28") (pintype "passive"))
    )
    (net (code "225") (name "TLPORT_D_BITS_DATA[25]") (class "Default")
      (node (ref "JP21") (pin "13") (pinfunction "13_13") (pintype "passive"))
      (node (ref "SOCKET_7") (pin "27") (pinfunction "27_27") (pintype "passive"))
    )
    (net (code "226") (name "TLPORT_D_BITS_DATA[26]") (class "Default")
      (node (ref "JP21") (pin "10") (pinfunction "10_10") (pintype "passive"))
      (node (ref "SOCKET_7") (pin "26") (pinfunction "26_26") (pintype "passive"))
    )
    (net (code "227") (name "TLPORT_D_BITS_DATA[27]") (class "Default")
      (node (ref "JP21") (pin "9") (pinfunction "9_9") (pintype "passive"))
      (node (ref "SOCKET_7") (pin "25") (pinfunction "25_25") (pintype "passive"))
    )
    (net (code "228") (name "TLPORT_D_BITS_DATA[28]") (class "Default")
      (node (ref "JP21") (pin "8") (pinfunction "8_8") (pintype "passive"))
      (node (ref "SOCKET_7") (pin "23") (pinfunction "23_23") (pintype "passive"))
    )
    (net (code "229") (name "TLPORT_D_BITS_DATA[29]") (class "Default")
      (node (ref "JP21") (pin "7") (pinfunction "7_7") (pintype "passive"))
      (node (ref "SOCKET_7") (pin "22") (pinfunction "22_22") (pintype "passive"))
    )
    (net (code "230") (name "TLPORT_D_BITS_DATA[30]") (class "Default")
      (node (ref "JP21") (pin "6") (pinfunction "6_6") (pintype "passive"))
      (node (ref "SOCKET_7") (pin "21") (pinfunction "21_21") (pintype "passive"))
    )
    (net (code "231") (name "TLPORT_D_BITS_DATA[31]") (class "Default")
      (node (ref "JP21") (pin "5") (pinfunction "5_5") (pintype "passive"))
      (node (ref "SOCKET_7") (pin "20") (pinfunction "20_20") (pintype "passive"))
    )
    (net (code "232") (name "TLPORT_D_BITS_DENIED") (class "Default")
      (node (ref "JP20") (pin "39") (pinfunction "39_39") (pintype "passive"))
      (node (ref "SOCKET_7") (pin "18") (pinfunction "18_18") (pintype "passive"))
    )
    (net (code "233") (name "TLPORT_D_BITS_OPCODE[0]") (class "Default")
      (node (ref "JP20") (pin "24") (pinfunction "24_24") (pintype "passive"))
      (node (ref "SOCKET_6") (pin "21") (pinfunction "21_21") (pintype "passive"))
    )
    (net (code "234") (name "TLPORT_D_BITS_OPCODE[1]") (class "Default")
      (node (ref "JP20") (pin "23") (pinfunction "23_23") (pintype "passive"))
      (node (ref "SOCKET_6") (pin "20") (pinfunction "20_20") (pintype "passive"))
    )
    (net (code "235") (name "TLPORT_D_BITS_OPCODE[2]") (class "Default")
      (node (ref "JP20") (pin "22") (pinfunction "22_22") (pintype "passive"))
      (node (ref "SOCKET_6") (pin "18") (pinfunction "18_18") (pintype "passive"))
    )
    (net (code "236") (name "TLPORT_D_BITS_PARAM[0]") (class "Default")
      (node (ref "JP20") (pin "26") (pinfunction "26_26") (pintype "passive"))
      (node (ref "SOCKET_6") (pin "24") (pinfunction "24_24") (pintype "passive"))
    )
    (net (code "237") (name "TLPORT_D_BITS_PARAM[1]") (class "Default")
      (node (ref "JP20") (pin "25") (pinfunction "25_25") (pintype "passive"))
      (node (ref "SOCKET_6") (pin "23") (pinfunction "23_23") (pintype "passive"))
    )
    (net (code "238") (name "TLPORT_D_BITS_SINK") (class "Default")
      (node (ref "JP20") (pin "38") (pinfunction "38_38") (pintype "passive"))
      (node (ref "SOCKET_7") (pin "17") (pinfunction "17_17") (pintype "passive"))
    )
    (net (code "239") (name "TLPORT_D_BITS_SIZE[0]") (class "Default")
      (node (ref "JP20") (pin "31") (pinfunction "31_31") (pintype "passive"))
      (node (ref "SOCKET_7") (pin "8") (pinfunction "8_8") (pintype "passive"))
    )
    (net (code "240") (name "TLPORT_D_BITS_SIZE[1]") (class "Default")
      (node (ref "JP20") (pin "28") (pinfunction "28_28") (pintype "passive"))
      (node (ref "SOCKET_7") (pin "7") (pinfunction "7_7") (pintype "passive"))
    )
    (net (code "241") (name "TLPORT_D_BITS_SIZE[2]") (class "Default")
      (node (ref "JP20") (pin "27") (pinfunction "27_27") (pintype "passive"))
      (node (ref "SOCKET_6") (pin "25") (pinfunction "25_25") (pintype "passive"))
    )
    (net (code "242") (name "TLPORT_D_BITS_SOURCE[0]") (class "Default")
      (node (ref "JP20") (pin "37") (pinfunction "37_37") (pintype "passive"))
      (node (ref "SOCKET_7") (pin "15") (pinfunction "15_15") (pintype "passive"))
    )
    (net (code "243") (name "TLPORT_D_BITS_SOURCE[1]") (class "Default")
      (node (ref "JP20") (pin "36") (pinfunction "36_36") (pintype "passive"))
      (node (ref "SOCKET_7") (pin "14") (pinfunction "14_14") (pintype "passive"))
    )
    (net (code "244") (name "TLPORT_D_BITS_SOURCE[2]") (class "Default")
      (node (ref "JP20") (pin "35") (pinfunction "35_35") (pintype "passive"))
      (node (ref "SOCKET_7") (pin "13") (pinfunction "13_13") (pintype "passive"))
    )
    (net (code "245") (name "TLPORT_D_BITS_SOURCE[3]") (class "Default")
      (node (ref "JP20") (pin "34") (pinfunction "34_34") (pintype "passive"))
      (node (ref "SOCKET_7") (pin "12") (pinfunction "12_12") (pintype "passive"))
    )
    (net (code "246") (name "TLPORT_D_BITS_SOURCE[4]") (class "Default")
      (node (ref "JP20") (pin "33") (pinfunction "33_33") (pintype "passive"))
      (node (ref "SOCKET_7") (pin "10") (pinfunction "10_10") (pintype "passive"))
    )
    (net (code "247") (name "TLPORT_D_BITS_SOURCE[5]") (class "Default")
      (node (ref "JP20") (pin "32") (pinfunction "32_32") (pintype "passive"))
      (node (ref "SOCKET_7") (pin "9") (pinfunction "9_9") (pintype "passive"))
    )
    (net (code "248") (name "TLPORT_D_READY") (class "Default")
      (node (ref "JP20") (pin "20") (pinfunction "20_20") (pintype "passive"))
      (node (ref "SOCKET_6") (pin "15") (pinfunction "15_15") (pintype "passive"))
    )
    (net (code "249") (name "TLPORT_D_VALID") (class "Default")
      (node (ref "JP20") (pin "21") (pinfunction "21_21") (pintype "passive"))
      (node (ref "SOCKET_6") (pin "17") (pinfunction "17_17") (pintype "passive"))
    )
    (net (code "250") (name "TMS") (class "Default")
      (node (ref "IC4") (pin "13") (pinfunction "B2_13") (pintype "bidirectional"))
      (node (ref "JTAG_20_PIN") (pin "7") (pinfunction "7_7") (pintype "passive"))
      (node (ref "R22") (pin "1") (pinfunction "1_1") (pintype "passive"))
    )
    (net (code "251") (name "UART_RXD") (class "Default")
      (node (ref "SOCKET_2") (pin "4") (pinfunction "4_4") (pintype "passive"))
      (node (ref "USB-UART") (pin "3") (pinfunction "3_3") (pintype "passive"))
    )
    (net (code "252") (name "UART_TXD") (class "Default")
      (node (ref "SOCKET_2") (pin "3") (pinfunction "3_3") (pintype "passive"))
      (node (ref "USB-UART") (pin "7") (pinfunction "7_7") (pintype "passive"))
    )
    (net (code "253") (name "USBCLK") (class "Default")
      (node (ref "SOCKET_8") (pin "26") (pinfunction "26_26") (pintype "passive"))
    )
    (net (code "254") (name "USBFULLSPEED") (class "Default")
      (node (ref "SOCKET_1") (pin "6") (pinfunction "6_6") (pintype "passive"))
    )
    (net (code "255") (name "USBWIRECTRLOUT") (class "Default")
      (node (ref "SOCKET_1") (pin "4") (pinfunction "4_4") (pintype "passive"))
    )
    (net (code "256") (name "USBWIREDATAIN[0]") (class "Default")
      (node (ref "SOCKET_8") (pin "30") (pinfunction "30_30") (pintype "passive"))
    )
    (net (code "257") (name "USBWIREDATAIN[1]") (class "Default")
      (node (ref "SOCKET_8") (pin "28") (pinfunction "28_28") (pintype "passive"))
    )
    (net (code "258") (name "USBWIREDATAOUT[0]") (class "Default")
      (node (ref "SOCKET_1") (pin "2") (pinfunction "2_2") (pintype "passive"))
    )
    (net (code "259") (name "USBWIREDATAOUT[1]") (class "Default")
      (node (ref "SOCKET_8") (pin "32") (pinfunction "32_32") (pintype "passive"))
    )
    (net (code "260") (name "VDD_1.8_1") (class "Default")
      (node (ref "C14") (pin "1") (pinfunction "1_1") (pintype "passive"))
      (node (ref "IC7") (pin "2") (pinfunction "OUTPUT_2") (pintype "bidirectional"))
      (node (ref "IC7") (pin "4") (pinfunction "VOUT_4") (pintype "bidirectional"))
      (node (ref "JP8") (pin "1") (pinfunction "1_1") (pintype "passive"))
      (node (ref "Q3") (pin "1") (pinfunction "G_1") (pintype "bidirectional"))
      (node (ref "R1") (pin "2") (pinfunction "2_2") (pintype "passive"))
      (node (ref "R63") (pin "2") (pinfunction "2_2") (pintype "passive"))
    )
    (net (code "261") (name "VDD_1.8_2") (class "Default")
      (node (ref "C16") (pin "1") (pinfunction "1_1") (pintype "passive"))
      (node (ref "IC8") (pin "2") (pinfunction "OUTPUT_2") (pintype "bidirectional"))
      (node (ref "IC8") (pin "4") (pinfunction "VOUT_4") (pintype "bidirectional"))
      (node (ref "JP8") (pin "5") (pinfunction "5_5") (pintype "passive"))
      (node (ref "Q4") (pin "1") (pinfunction "G_1") (pintype "bidirectional"))
      (node (ref "R3") (pin "2") (pinfunction "2_2") (pintype "passive"))
      (node (ref "R61") (pin "2") (pinfunction "2_2") (pintype "passive"))
    )
    (net (code "262") (name "VDD_1.8_3") (class "Default")
      (node (ref "C18") (pin "1") (pinfunction "1_1") (pintype "passive"))
      (node (ref "IC9") (pin "2") (pinfunction "OUTPUT_2") (pintype "bidirectional"))
      (node (ref "IC9") (pin "4") (pinfunction "VOUT_4") (pintype "bidirectional"))
      (node (ref "JP8") (pin "7") (pinfunction "7_7") (pintype "passive"))
      (node (ref "Q5") (pin "1") (pinfunction "G_1") (pintype "bidirectional"))
      (node (ref "R5") (pin "2") (pinfunction "2_2") (pintype "passive"))
      (node (ref "R62") (pin "2") (pinfunction "2_2") (pintype "passive"))
    )
    (net (code "263") (name "VDD_1V8") (class "Default")
      (node (ref "C3") (pin "1") (pinfunction "1_1") (pintype "passive"))
      (node (ref "C5") (pin "1") (pinfunction "1_1") (pintype "passive"))
      (node (ref "C8") (pin "1") (pinfunction "1_1") (pintype "passive"))
      (node (ref "IC1") (pin "1") (pinfunction "DIR1_1") (pintype "bidirectional"))
      (node (ref "IC1") (pin "16") (pinfunction "VCCA_16") (pintype "bidirectional"))
      (node (ref "IC1") (pin "2") (pinfunction "DIR2_2") (pintype "bidirectional"))
      (node (ref "IC1") (pin "7") (pinfunction "DIR3_7") (pintype "bidirectional"))
      (node (ref "IC3") (pin "1") (pinfunction "DIR1_1") (pintype "bidirectional"))
      (node (ref "IC3") (pin "16") (pinfunction "VCCA_16") (pintype "bidirectional"))
      (node (ref "IC3") (pin "7") (pinfunction "DIR3_7") (pintype "bidirectional"))
      (node (ref "IC3") (pin "8") (pinfunction "DIR4_8") (pintype "bidirectional"))
      (node (ref "IC4") (pin "16") (pinfunction "VCCA_16") (pintype "bidirectional"))
      (node (ref "IC4") (pin "8") (pinfunction "DIR4_8") (pintype "bidirectional"))
      (node (ref "JP8") (pin "2") (pinfunction "2_2") (pintype "passive"))
      (node (ref "R26") (pin "2") (pinfunction "2_2") (pintype "passive"))
      (node (ref "R27") (pin "2") (pinfunction "2_2") (pintype "passive"))
      (node (ref "R28") (pin "2") (pinfunction "2_2") (pintype "passive"))
      (node (ref "R29") (pin "2") (pinfunction "2_2") (pintype "passive"))
      (node (ref "R30") (pin "2") (pinfunction "2_2") (pintype "passive"))
      (node (ref "R31") (pin "2") (pinfunction "2_2") (pintype "passive"))
      (node (ref "R32") (pin "2") (pinfunction "2_2") (pintype "passive"))
      (node (ref "R33") (pin "2") (pinfunction "2_2") (pintype "passive"))
      (node (ref "R58") (pin "2") (pinfunction "2_2") (pintype "passive"))
      (node (ref "R59") (pin "2") (pinfunction "2_2") (pintype "passive"))
      (node (ref "R60") (pin "2") (pinfunction "2_2") (pintype "passive"))
      (node (ref "USB-UART") (pin "5") (pinfunction "5_5") (pintype "passive"))
    )
    (net (code "264") (name "VDD_3V3") (class "Default")
      (node (ref "C13") (pin "1") (pinfunction "1_1") (pintype "passive"))
      (node (ref "C15") (pin "1") (pinfunction "1_1") (pintype "passive"))
      (node (ref "C17") (pin "1") (pinfunction "1_1") (pintype "passive"))
      (node (ref "C2") (pin "1") (pinfunction "1_1") (pintype "passive"))
      (node (ref "C4") (pin "1") (pinfunction "1_1") (pintype "passive"))
      (node (ref "C7") (pin "1") (pinfunction "1_1") (pintype "passive"))
      (node (ref "FLASH") (pin "1") (pinfunction "1_1") (pintype "passive"))
      (node (ref "FLASH") (pin "2") (pinfunction "2_2") (pintype "passive"))
      (node (ref "IC1") (pin "15") (pinfunction "VCCB_15") (pintype "bidirectional"))
      (node (ref "IC3") (pin "15") (pinfunction "VCCB_15") (pintype "bidirectional"))
      (node (ref "IC4") (pin "15") (pinfunction "VCCB_15") (pintype "bidirectional"))
      (node (ref "IC7") (pin "3") (pinfunction "INPUT_3") (pintype "bidirectional"))
      (node (ref "IC8") (pin "3") (pinfunction "INPUT_3") (pintype "bidirectional"))
      (node (ref "IC9") (pin "3") (pinfunction "INPUT_3") (pintype "bidirectional"))
      (node (ref "JP8") (pin "3") (pinfunction "3_3") (pintype "passive"))
      (node (ref "JTAG_20_PIN") (pin "1") (pinfunction "1_1") (pintype "passive"))
      (node (ref "JTAG_20_PIN") (pin "2") (pinfunction "2_2") (pintype "passive"))
      (node (ref "R22") (pin "2") (pinfunction "2_2") (pintype "passive"))
      (node (ref "R23") (pin "2") (pinfunction "2_2") (pintype "passive"))
      (node (ref "R24") (pin "2") (pinfunction "2_2") (pintype "passive"))
      (node (ref "R25") (pin "2") (pinfunction "2_2") (pintype "passive"))
      (node (ref "R46") (pin "2") (pinfunction "2_2") (pintype "passive"))
      (node (ref "R47") (pin "2") (pinfunction "2_2") (pintype "passive"))
      (node (ref "R48") (pin "2") (pinfunction "2_2") (pintype "passive"))
      (node (ref "R49") (pin "2") (pinfunction "2_2") (pintype "passive"))
      (node (ref "R50") (pin "2") (pinfunction "2_2") (pintype "passive"))
      (node (ref "R51") (pin "2") (pinfunction "2_2") (pintype "passive"))
      (node (ref "R52") (pin "2") (pinfunction "2_2") (pintype "passive"))
      (node (ref "R53") (pin "2") (pinfunction "2_2") (pintype "passive"))
      (node (ref "R54") (pin "2") (pinfunction "2_2") (pintype "passive"))
      (node (ref "R55") (pin "2") (pinfunction "2_2") (pintype "passive"))
      (node (ref "R56") (pin "2") (pinfunction "2_2") (pintype "passive"))
      (node (ref "R57") (pin "2") (pinfunction "2_2") (pintype "passive"))
      (node (ref "SD_CARD") (pin "1") (pinfunction "1_1") (pintype "passive"))
      (node (ref "SD_CARD") (pin "2") (pinfunction "2_2") (pintype "passive"))
    )
    (net (code "265") (name "VDD_3V3_GPIO") (class "Default")
      (node (ref "JP18") (pin "29") (pinfunction "29_29") (pintype "passive"))
      (node (ref "JP19") (pin "29") (pinfunction "29_29") (pintype "passive"))
      (node (ref "JP20") (pin "29") (pinfunction "29_29") (pintype "passive"))
      (node (ref "JP21") (pin "29") (pinfunction "29_29") (pintype "passive"))
      (node (ref "JP8") (pin "4") (pinfunction "4_4") (pintype "passive"))
    )
    (net (code "266") (name "VDD_CHIP") (class "Default")
      (node (ref "C19") (pin "1") (pinfunction "1_1") (pintype "passive"))
      (node (ref "C20") (pin "1") (pinfunction "1_1") (pintype "passive"))
      (node (ref "JP8") (pin "6") (pinfunction "6_6") (pintype "passive"))
      (node (ref "SOCKET_1") (pin "16") (pinfunction "16_16") (pintype "passive"))
      (node (ref "SOCKET_2") (pin "16") (pinfunction "16_16") (pintype "passive"))
      (node (ref "SOCKET_3") (pin "16") (pinfunction "16_16") (pintype "passive"))
      (node (ref "SOCKET_4") (pin "16") (pinfunction "16_16") (pintype "passive"))
      (node (ref "SOCKET_5") (pin "16") (pinfunction "16_16") (pintype "passive"))
      (node (ref "SOCKET_6") (pin "16") (pinfunction "16_16") (pintype "passive"))
      (node (ref "SOCKET_7") (pin "16") (pinfunction "16_16") (pintype "passive"))
      (node (ref "SOCKET_8") (pin "16") (pinfunction "16_16") (pintype "passive"))
    )
    (net (code "267") (name "VDD_CHIP_IO") (class "Default")
      (node (ref "C21") (pin "1") (pinfunction "1_1") (pintype "passive"))
      (node (ref "C22") (pin "1") (pinfunction "1_1") (pintype "passive"))
      (node (ref "JP8") (pin "8") (pinfunction "8_8") (pintype "passive"))
      (node (ref "SOCKET_1") (pin "24") (pinfunction "24_24") (pintype "passive"))
      (node (ref "SOCKET_2") (pin "19") (pinfunction "19_19") (pintype "passive"))
      (node (ref "SOCKET_3") (pin "24") (pinfunction "24_24") (pintype "passive"))
      (node (ref "SOCKET_4") (pin "19") (pinfunction "19_19") (pintype "passive"))
      (node (ref "SOCKET_5") (pin "24") (pinfunction "24_24") (pintype "passive"))
      (node (ref "SOCKET_6") (pin "19") (pinfunction "19_19") (pintype "passive"))
      (node (ref "SOCKET_7") (pin "24") (pinfunction "24_24") (pintype "passive"))
      (node (ref "SOCKET_8") (pin "19") (pinfunction "19_19") (pintype "passive"))
    )
    (net (code "268") (name "unconnected-(FLASH-Pad9)") (class "Default")
      (node (ref "FLASH") (pin "9") (pinfunction "9_9") (pintype "passive"))
    )
    (net (code "269") (name "unconnected-(FLASH-Pad11)") (class "Default")
      (node (ref "FLASH") (pin "11") (pinfunction "11_11") (pintype "passive"))
    )
    (net (code "270") (name "unconnected-(JP18-Pad11)") (class "Default")
      (node (ref "JP18") (pin "11") (pinfunction "11_11") (pintype "passive"))
    )
    (net (code "271") (name "unconnected-(JP19-Pad11)") (class "Default")
      (node (ref "JP19") (pin "11") (pinfunction "11_11") (pintype "passive"))
    )
    (net (code "272") (name "unconnected-(JP20-Pad11)") (class "Default")
      (node (ref "JP20") (pin "11") (pinfunction "11_11") (pintype "passive"))
    )
    (net (code "273") (name "unconnected-(JP21-Pad1)") (class "Default")
      (node (ref "JP21") (pin "1") (pinfunction "1_1") (pintype "passive"))
    )
    (net (code "274") (name "unconnected-(JP21-Pad3)") (class "Default")
      (node (ref "JP21") (pin "3") (pinfunction "3_3") (pintype "passive"))
    )
    (net (code "275") (name "unconnected-(JP21-Pad11)") (class "Default")
      (node (ref "JP21") (pin "11") (pinfunction "11_11") (pintype "passive"))
    )
    (net (code "276") (name "unconnected-(JTAG_20_PIN-Pad3)") (class "Default")
      (node (ref "JTAG_20_PIN") (pin "3") (pinfunction "3_3") (pintype "passive"))
    )
    (net (code "277") (name "unconnected-(JTAG_20_PIN-Pad11)") (class "Default")
      (node (ref "JTAG_20_PIN") (pin "11") (pinfunction "11_11") (pintype "passive"))
    )
    (net (code "278") (name "unconnected-(JTAG_20_PIN-Pad15)") (class "Default")
      (node (ref "JTAG_20_PIN") (pin "15") (pinfunction "15_15") (pintype "passive"))
    )
    (net (code "279") (name "unconnected-(JTAG_20_PIN-Pad17)") (class "Default")
      (node (ref "JTAG_20_PIN") (pin "17") (pinfunction "17_17") (pintype "passive"))
    )
    (net (code "280") (name "unconnected-(JTAG_20_PIN-Pad19)") (class "Default")
      (node (ref "JTAG_20_PIN") (pin "19") (pinfunction "19_19") (pintype "passive"))
    )
    (net (code "281") (name "unconnected-(SD_CARD-Pad5)") (class "Default")
      (node (ref "SD_CARD") (pin "5") (pinfunction "5_5") (pintype "passive"))
    )
    (net (code "282") (name "unconnected-(SOCKET_1-Pad1)") (class "Default")
      (node (ref "SOCKET_1") (pin "1") (pinfunction "1_1") (pintype "passive"))
    )
    (net (code "283") (name "unconnected-(SOCKET_1-Pad3)") (class "Default")
      (node (ref "SOCKET_1") (pin "3") (pinfunction "3_3") (pintype "passive"))
    )
    (net (code "284") (name "unconnected-(SOCKET_1-Pad5)") (class "Default")
      (node (ref "SOCKET_1") (pin "5") (pinfunction "5_5") (pintype "passive"))
    )
    (net (code "285") (name "unconnected-(SOCKET_2-Pad12)") (class "Default")
      (node (ref "SOCKET_2") (pin "12") (pinfunction "12_12") (pintype "passive"))
    )
    (net (code "286") (name "unconnected-(SOCKET_2-Pad13)") (class "Default")
      (node (ref "SOCKET_2") (pin "13") (pinfunction "13_13") (pintype "passive"))
    )
    (net (code "287") (name "unconnected-(SOCKET_2-Pad28)") (class "Default")
      (node (ref "SOCKET_2") (pin "28") (pinfunction "28_28") (pintype "passive"))
    )
    (net (code "288") (name "unconnected-(SOCKET_2-Pad29)") (class "Default")
      (node (ref "SOCKET_2") (pin "29") (pinfunction "29_29") (pintype "passive"))
    )
    (net (code "289") (name "unconnected-(SOCKET_2-Pad30)") (class "Default")
      (node (ref "SOCKET_2") (pin "30") (pinfunction "30_30") (pintype "passive"))
    )
    (net (code "290") (name "unconnected-(SOCKET_2-Pad31)") (class "Default")
      (node (ref "SOCKET_2") (pin "31") (pinfunction "31_31") (pintype "passive"))
    )
    (net (code "291") (name "unconnected-(SOCKET_2-Pad32)") (class "Default")
      (node (ref "SOCKET_2") (pin "32") (pinfunction "32_32") (pintype "passive"))
    )
    (net (code "292") (name "unconnected-(SOCKET_3-Pad1)") (class "Default")
      (node (ref "SOCKET_3") (pin "1") (pinfunction "1_1") (pintype "passive"))
    )
    (net (code "293") (name "unconnected-(SOCKET_3-Pad2)") (class "Default")
      (node (ref "SOCKET_3") (pin "2") (pinfunction "2_2") (pintype "passive"))
    )
    (net (code "294") (name "unconnected-(SOCKET_3-Pad3)") (class "Default")
      (node (ref "SOCKET_3") (pin "3") (pinfunction "3_3") (pintype "passive"))
    )
    (net (code "295") (name "unconnected-(SOCKET_3-Pad4)") (class "Default")
      (node (ref "SOCKET_3") (pin "4") (pinfunction "4_4") (pintype "passive"))
    )
    (net (code "296") (name "unconnected-(SOCKET_3-Pad5)") (class "Default")
      (node (ref "SOCKET_3") (pin "5") (pinfunction "5_5") (pintype "passive"))
    )
    (net (code "297") (name "unconnected-(SOCKET_3-Pad6)") (class "Default")
      (node (ref "SOCKET_3") (pin "6") (pinfunction "6_6") (pintype "passive"))
    )
    (net (code "298") (name "unconnected-(SOCKET_4-Pad26)") (class "Default")
      (node (ref "SOCKET_4") (pin "26") (pinfunction "26_26") (pintype "passive"))
    )
    (net (code "299") (name "unconnected-(SOCKET_4-Pad27)") (class "Default")
      (node (ref "SOCKET_4") (pin "27") (pinfunction "27_27") (pintype "passive"))
    )
    (net (code "300") (name "unconnected-(SOCKET_4-Pad28)") (class "Default")
      (node (ref "SOCKET_4") (pin "28") (pinfunction "28_28") (pintype "passive"))
    )
    (net (code "301") (name "unconnected-(SOCKET_4-Pad29)") (class "Default")
      (node (ref "SOCKET_4") (pin "29") (pinfunction "29_29") (pintype "passive"))
    )
    (net (code "302") (name "unconnected-(SOCKET_4-Pad30)") (class "Default")
      (node (ref "SOCKET_4") (pin "30") (pinfunction "30_30") (pintype "passive"))
    )
    (net (code "303") (name "unconnected-(SOCKET_4-Pad31)") (class "Default")
      (node (ref "SOCKET_4") (pin "31") (pinfunction "31_31") (pintype "passive"))
    )
    (net (code "304") (name "unconnected-(SOCKET_4-Pad32)") (class "Default")
      (node (ref "SOCKET_4") (pin "32") (pinfunction "32_32") (pintype "passive"))
    )
    (net (code "305") (name "unconnected-(SOCKET_5-Pad1)") (class "Default")
      (node (ref "SOCKET_5") (pin "1") (pinfunction "1_1") (pintype "passive"))
    )
    (net (code "306") (name "unconnected-(SOCKET_5-Pad2)") (class "Default")
      (node (ref "SOCKET_5") (pin "2") (pinfunction "2_2") (pintype "passive"))
    )
    (net (code "307") (name "unconnected-(SOCKET_5-Pad3)") (class "Default")
      (node (ref "SOCKET_5") (pin "3") (pinfunction "3_3") (pintype "passive"))
    )
    (net (code "308") (name "unconnected-(SOCKET_5-Pad4)") (class "Default")
      (node (ref "SOCKET_5") (pin "4") (pinfunction "4_4") (pintype "passive"))
    )
    (net (code "309") (name "unconnected-(SOCKET_5-Pad5)") (class "Default")
      (node (ref "SOCKET_5") (pin "5") (pinfunction "5_5") (pintype "passive"))
    )
    (net (code "310") (name "unconnected-(SOCKET_5-Pad6)") (class "Default")
      (node (ref "SOCKET_5") (pin "6") (pinfunction "6_6") (pintype "passive"))
    )
    (net (code "311") (name "unconnected-(SOCKET_6-Pad26)") (class "Default")
      (node (ref "SOCKET_6") (pin "26") (pinfunction "26_26") (pintype "passive"))
    )
    (net (code "312") (name "unconnected-(SOCKET_6-Pad27)") (class "Default")
      (node (ref "SOCKET_6") (pin "27") (pinfunction "27_27") (pintype "passive"))
    )
    (net (code "313") (name "unconnected-(SOCKET_6-Pad28)") (class "Default")
      (node (ref "SOCKET_6") (pin "28") (pinfunction "28_28") (pintype "passive"))
    )
    (net (code "314") (name "unconnected-(SOCKET_6-Pad29)") (class "Default")
      (node (ref "SOCKET_6") (pin "29") (pinfunction "29_29") (pintype "passive"))
    )
    (net (code "315") (name "unconnected-(SOCKET_6-Pad30)") (class "Default")
      (node (ref "SOCKET_6") (pin "30") (pinfunction "30_30") (pintype "passive"))
    )
    (net (code "316") (name "unconnected-(SOCKET_6-Pad31)") (class "Default")
      (node (ref "SOCKET_6") (pin "31") (pinfunction "31_31") (pintype "passive"))
    )
    (net (code "317") (name "unconnected-(SOCKET_6-Pad32)") (class "Default")
      (node (ref "SOCKET_6") (pin "32") (pinfunction "32_32") (pintype "passive"))
    )
    (net (code "318") (name "unconnected-(SOCKET_7-Pad1)") (class "Default")
      (node (ref "SOCKET_7") (pin "1") (pinfunction "1_1") (pintype "passive"))
    )
    (net (code "319") (name "unconnected-(SOCKET_7-Pad2)") (class "Default")
      (node (ref "SOCKET_7") (pin "2") (pinfunction "2_2") (pintype "passive"))
    )
    (net (code "320") (name "unconnected-(SOCKET_7-Pad3)") (class "Default")
      (node (ref "SOCKET_7") (pin "3") (pinfunction "3_3") (pintype "passive"))
    )
    (net (code "321") (name "unconnected-(SOCKET_7-Pad4)") (class "Default")
      (node (ref "SOCKET_7") (pin "4") (pinfunction "4_4") (pintype "passive"))
    )
    (net (code "322") (name "unconnected-(SOCKET_7-Pad5)") (class "Default")
      (node (ref "SOCKET_7") (pin "5") (pinfunction "5_5") (pintype "passive"))
    )
    (net (code "323") (name "unconnected-(SOCKET_7-Pad6)") (class "Default")
      (node (ref "SOCKET_7") (pin "6") (pinfunction "6_6") (pintype "passive"))
    )
    (net (code "324") (name "unconnected-(SOCKET_8-Pad27)") (class "Default")
      (node (ref "SOCKET_8") (pin "27") (pinfunction "27_27") (pintype "passive"))
    )
    (net (code "325") (name "unconnected-(SOCKET_8-Pad29)") (class "Default")
      (node (ref "SOCKET_8") (pin "29") (pinfunction "29_29") (pintype "passive"))
    )
    (net (code "326") (name "unconnected-(SOCKET_8-Pad31)") (class "Default")
      (node (ref "SOCKET_8") (pin "31") (pinfunction "31_31") (pintype "passive"))
    )
    (net (code "327") (name "unconnected-(USB-UART-Pad2)") (class "Default")
      (node (ref "USB-UART") (pin "2") (pinfunction "2_2") (pintype "passive"))
    )
    (net (code "328") (name "unconnected-(USB-UART-Pad4)") (class "Default")
      (node (ref "USB-UART") (pin "4") (pinfunction "4_4") (pintype "passive"))
    )
    (net (code "329") (name "unconnected-(USB-UART-Pad6)") (class "Default")
      (node (ref "USB-UART") (pin "6") (pinfunction "6_6") (pintype "passive"))
    )
    (net (code "330") (name "unconnected-(USB-UART-Pad8)") (class "Default")
      (node (ref "USB-UART") (pin "8") (pinfunction "8_8") (pintype "passive"))
    )
  )
)
